# Hive_Max_Masse_neu4a.net
KiCad netlist of a schematic drawn in EAGLE
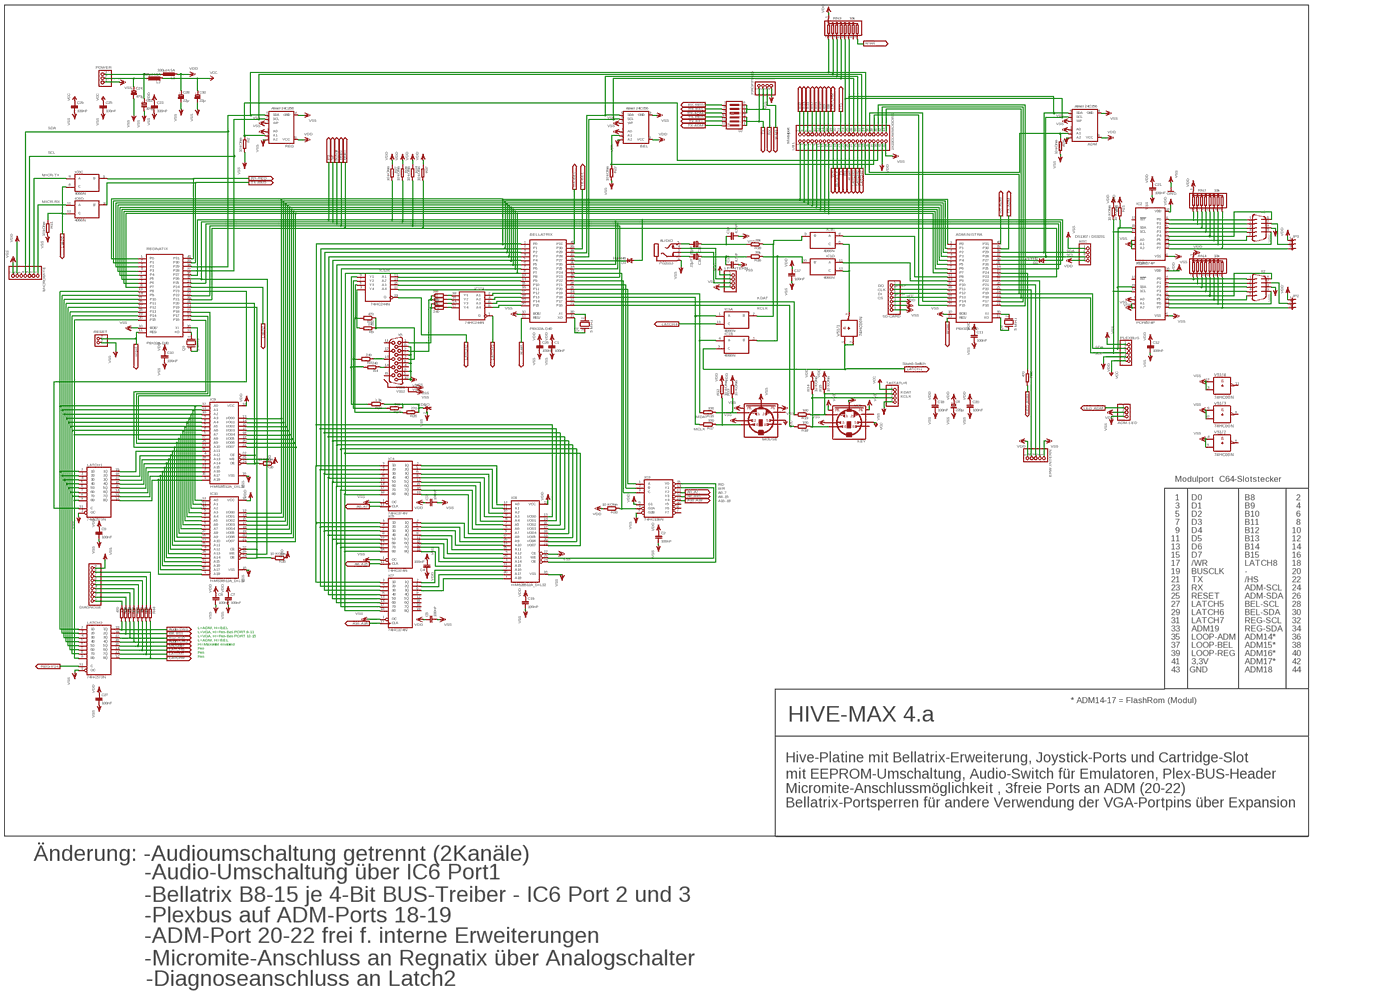
[diagram p0: schematic, sheet 1, overview]
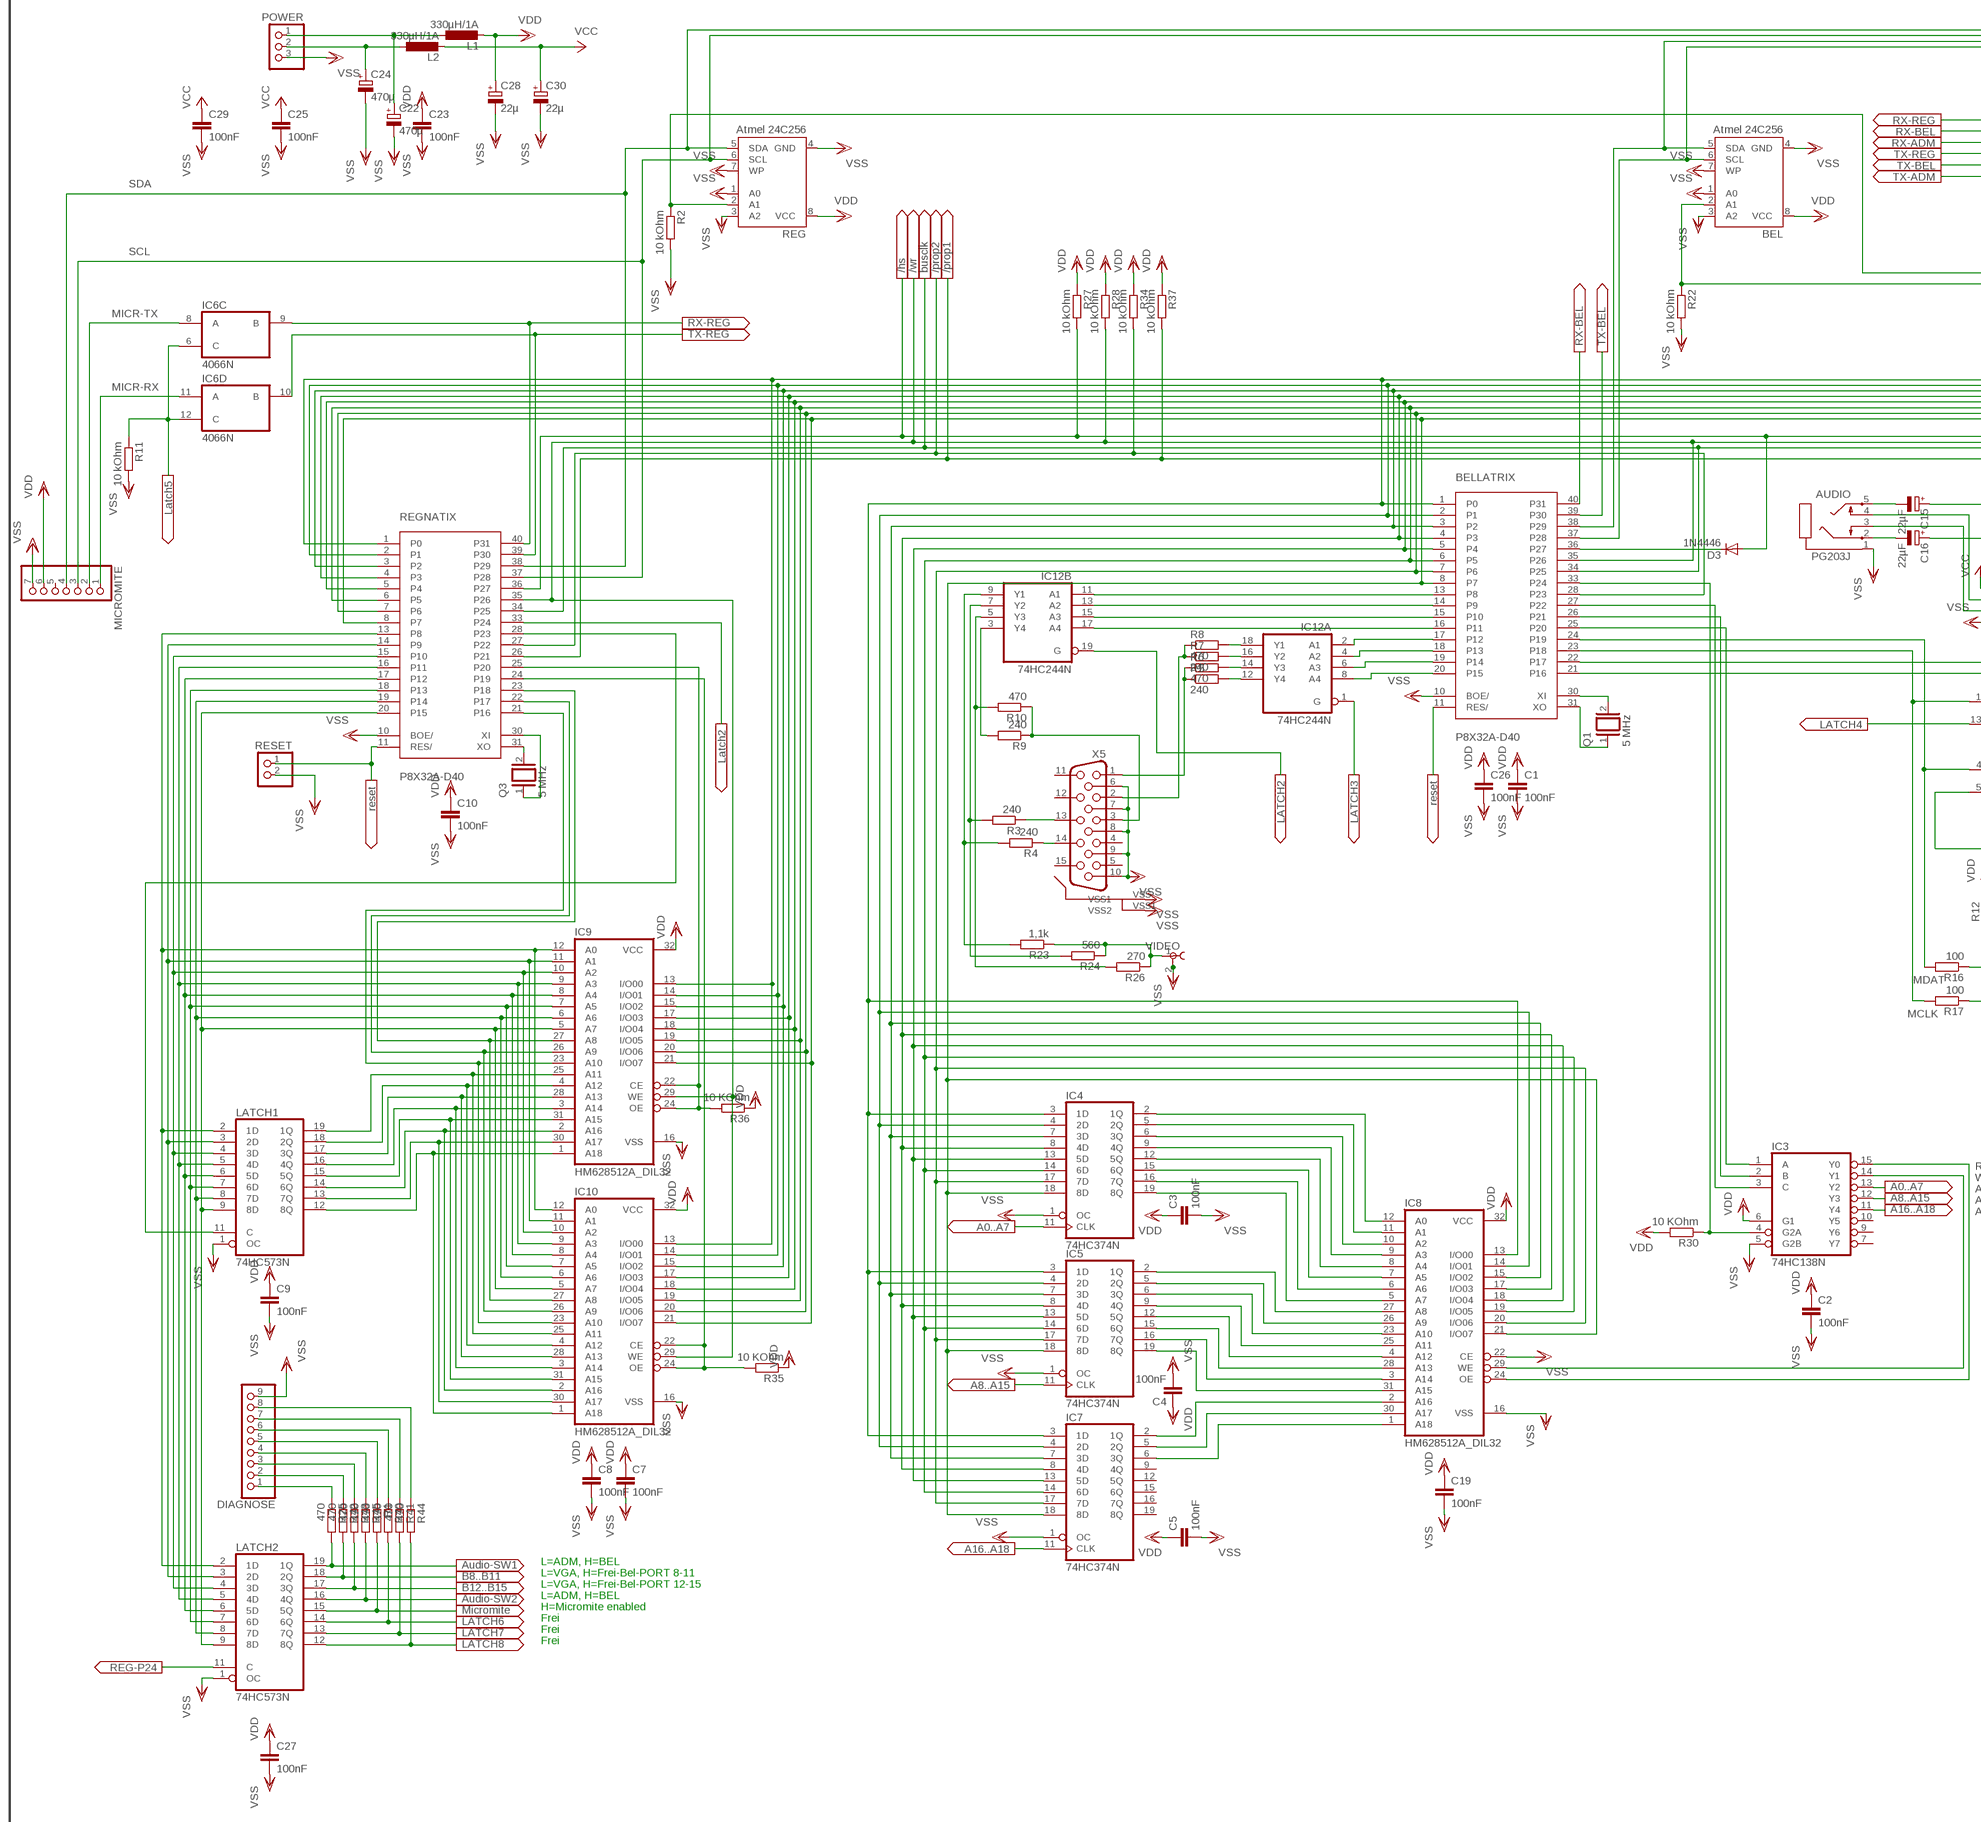
[diagram p1: schematic, sheet 1, part 1 of 4]
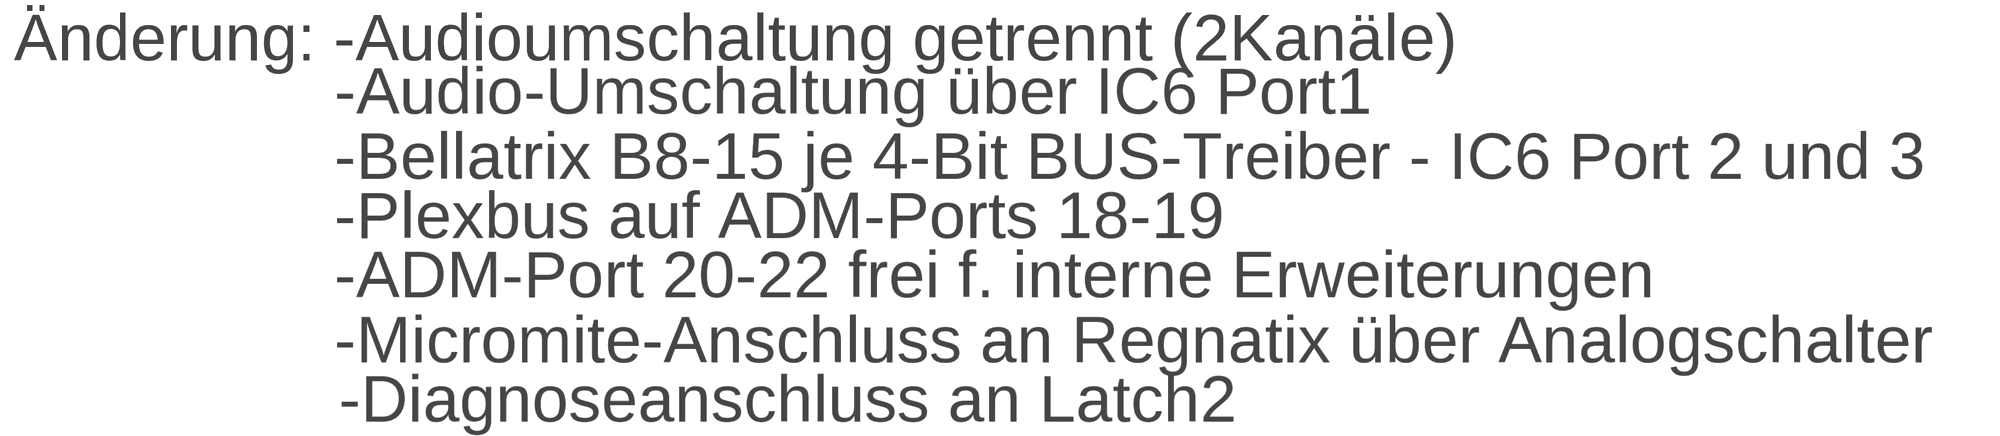
[diagram p2: schematic, sheet 1, part 2 of 4]
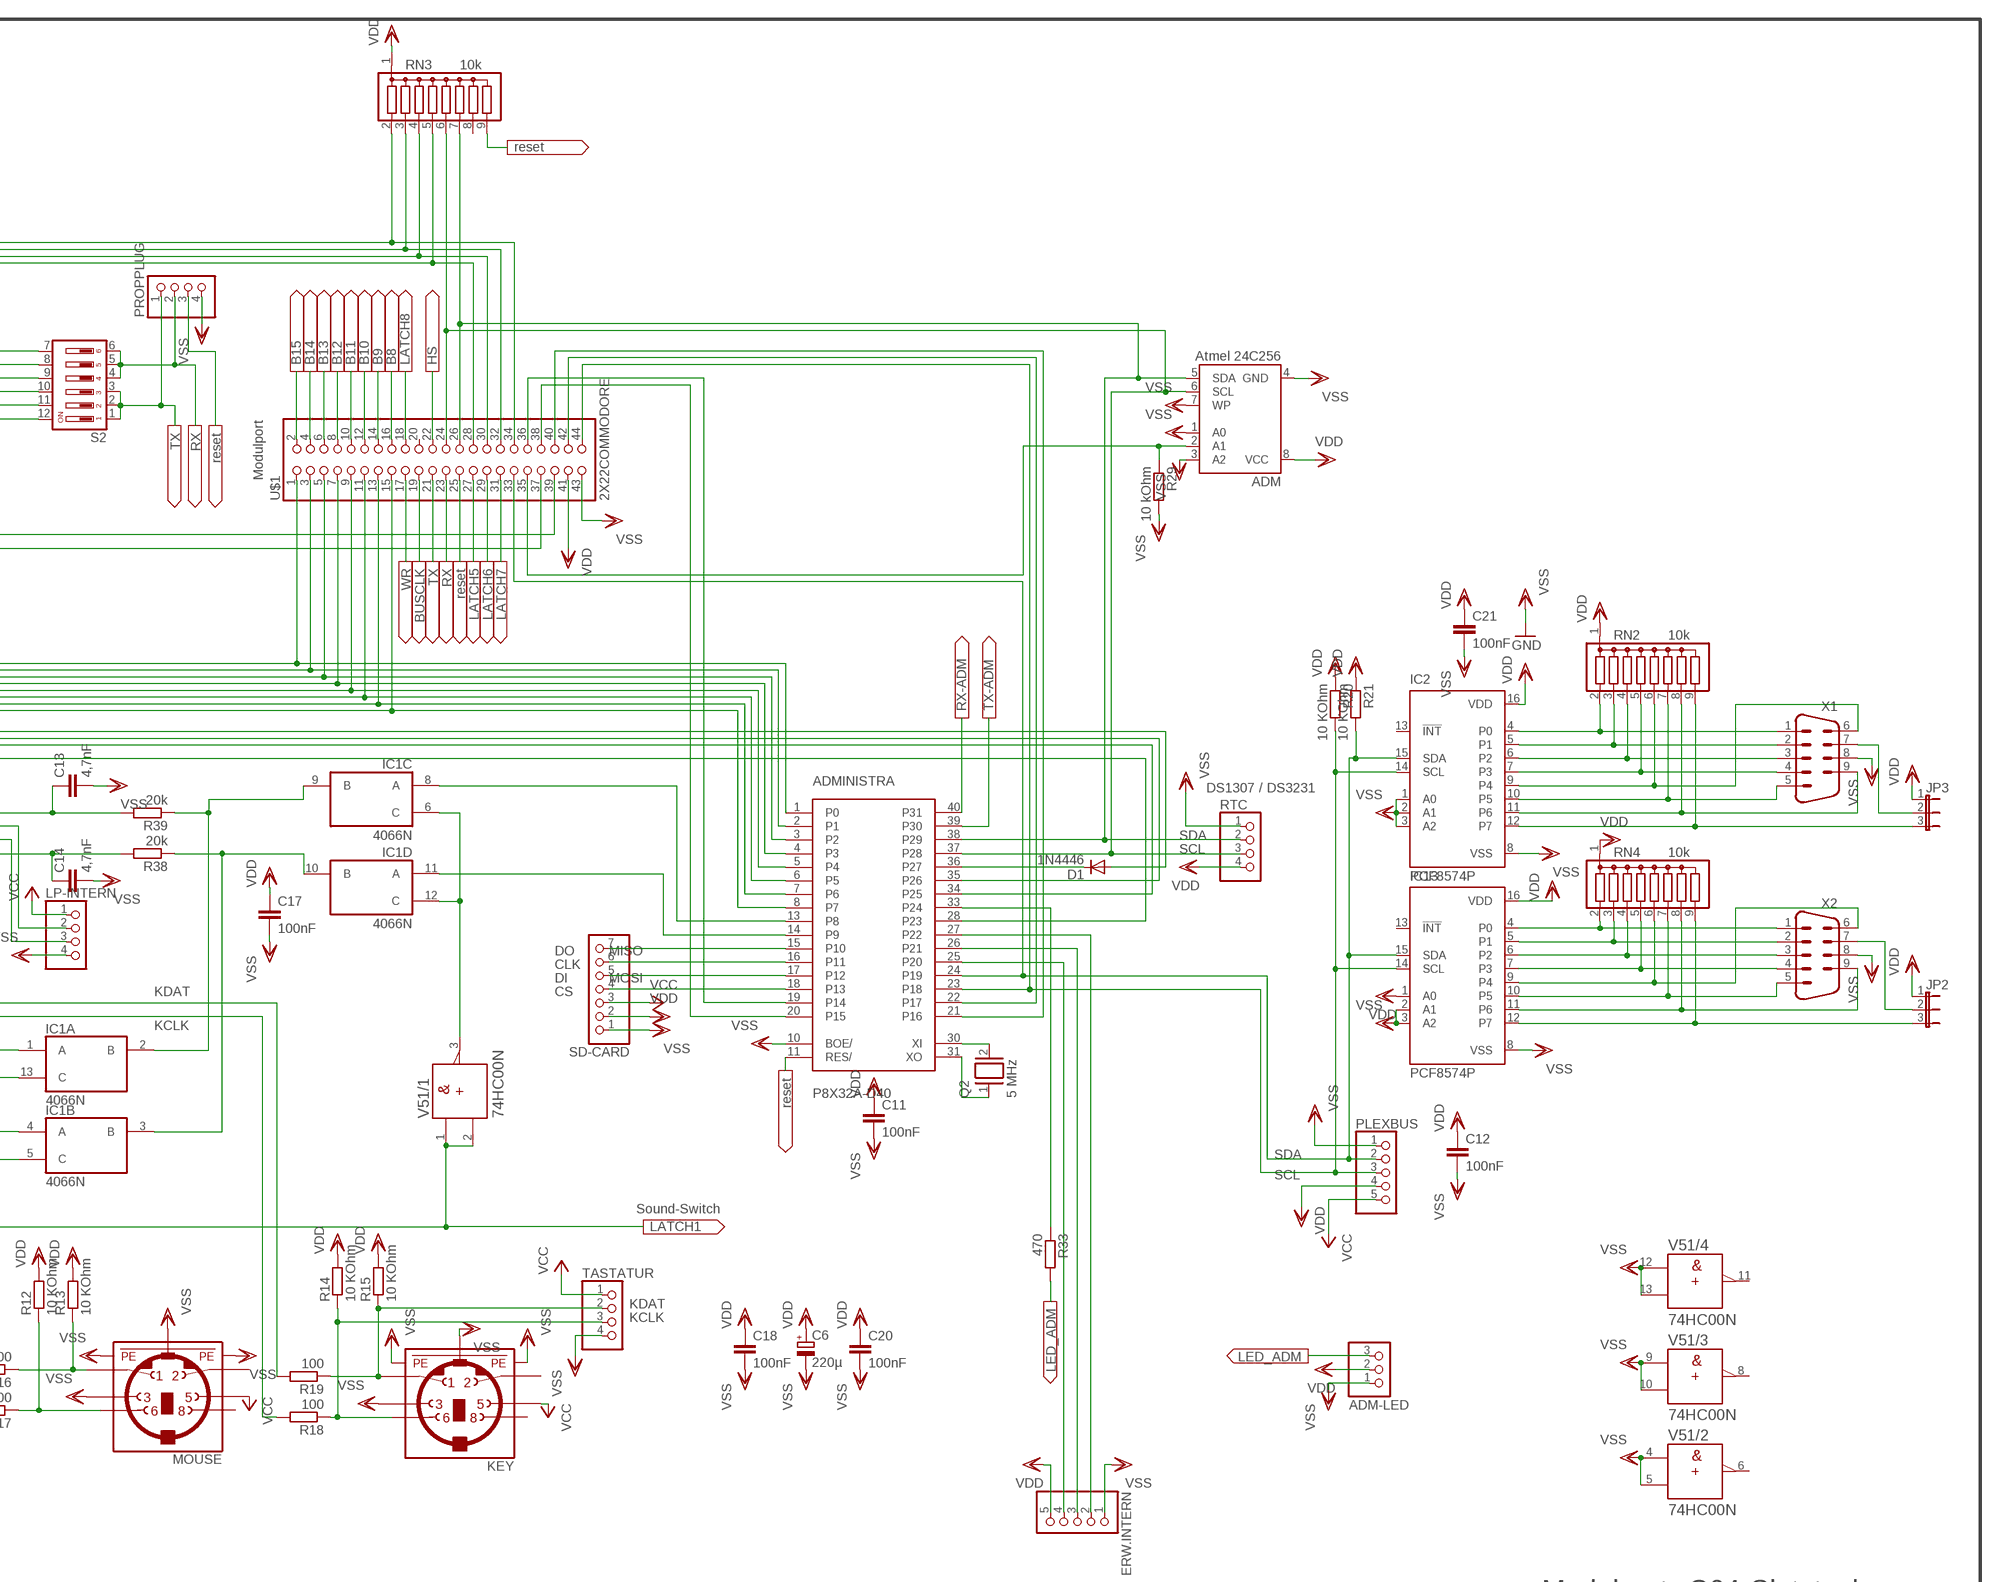
[diagram p3: schematic, sheet 1, part 3 of 4]
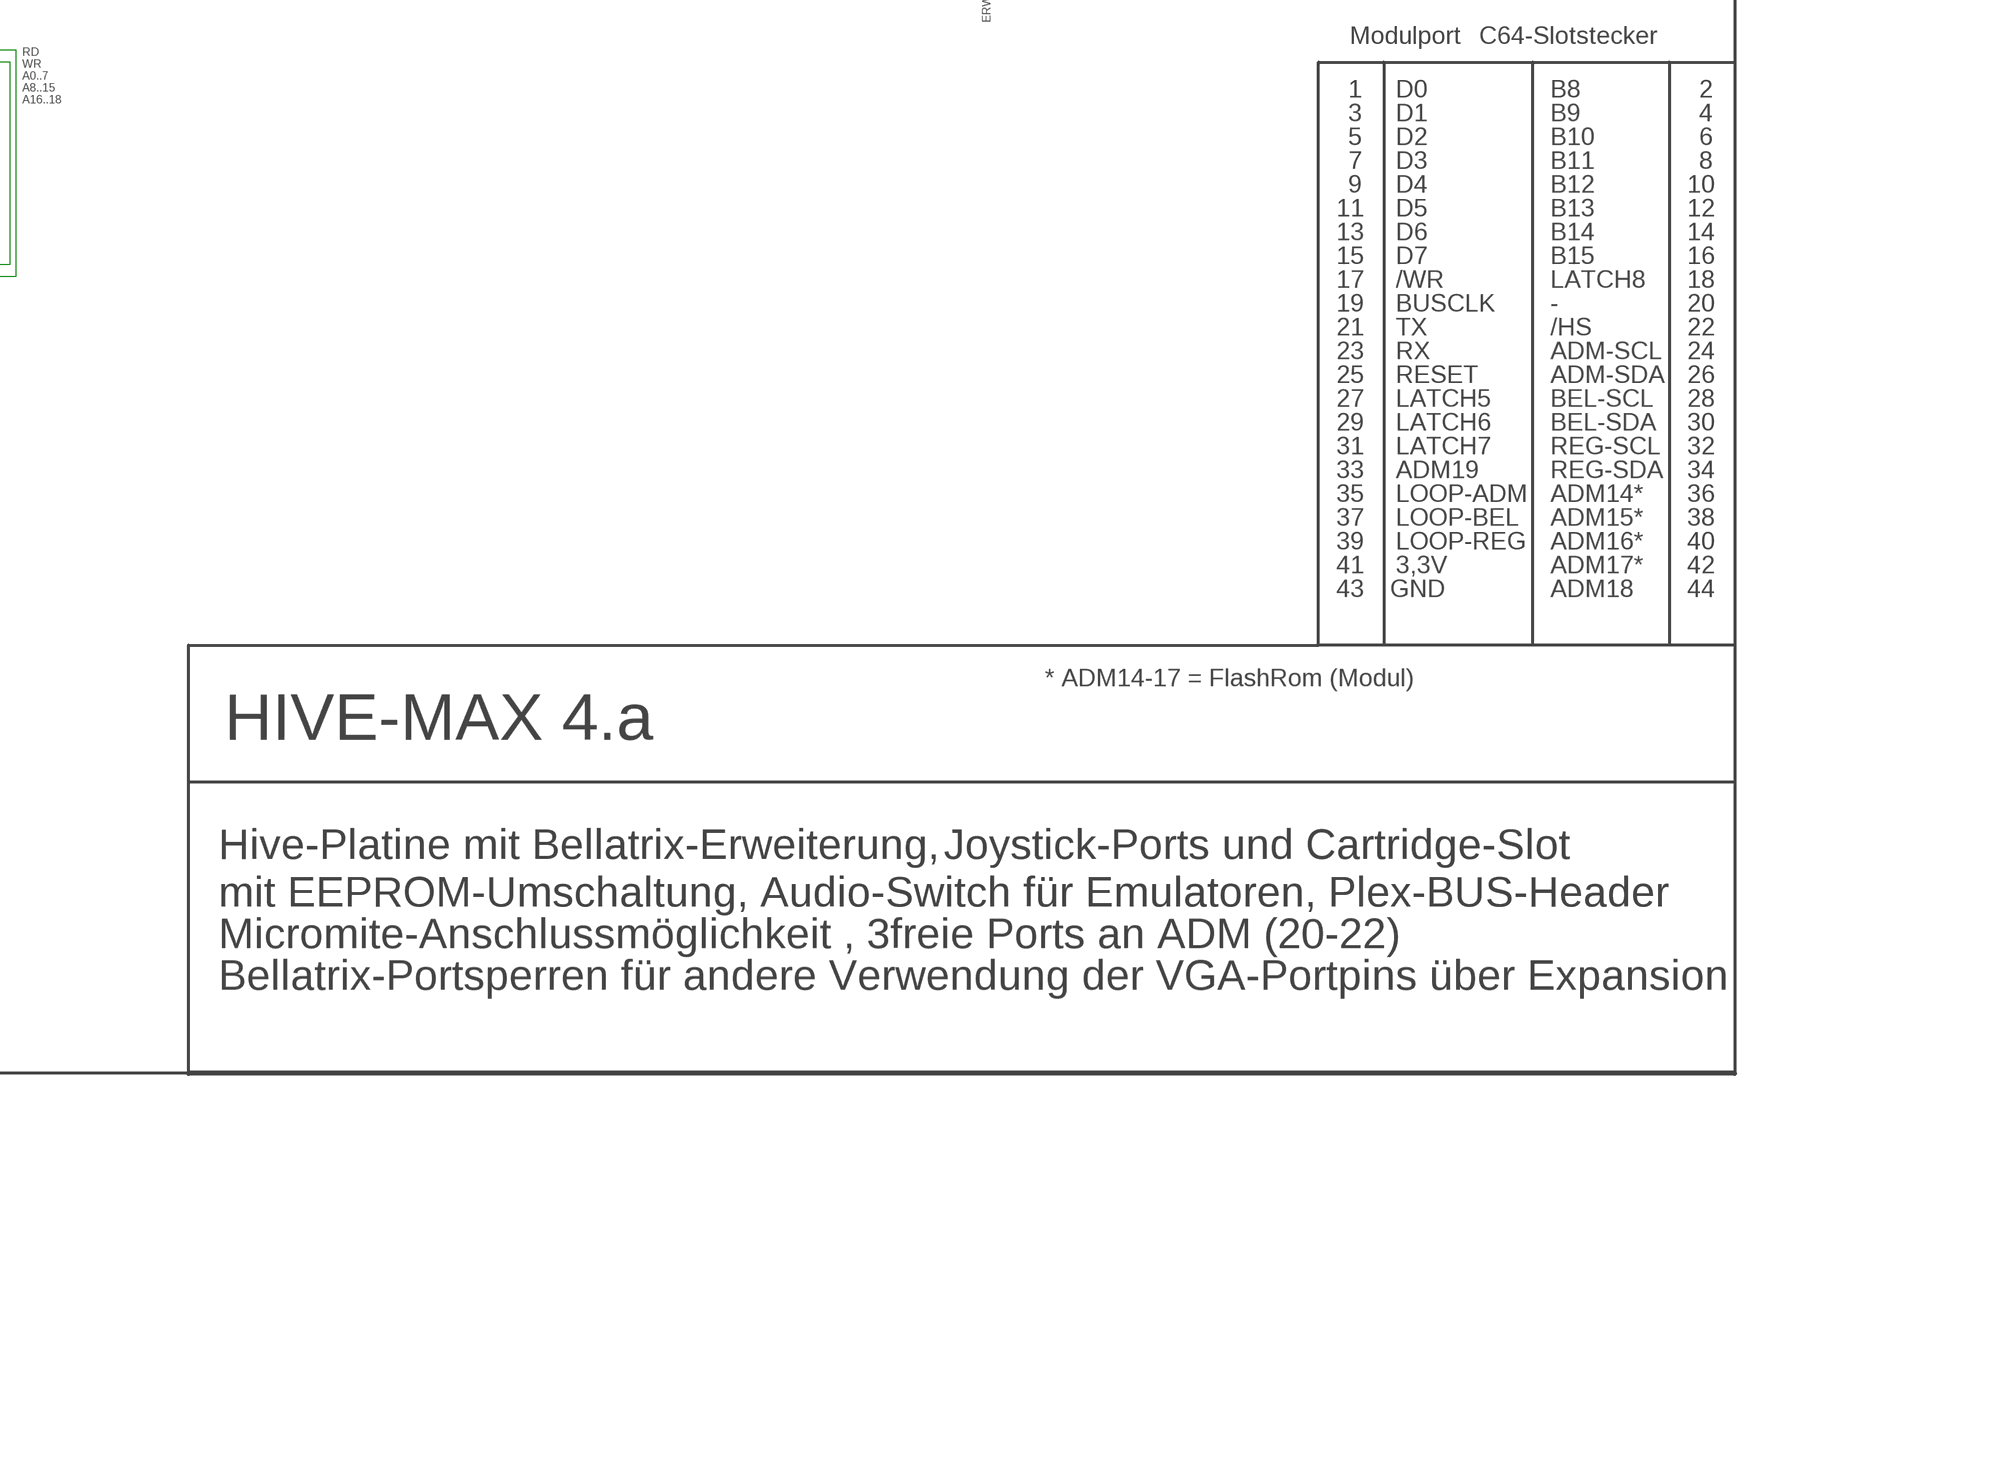
[diagram p4: schematic, sheet 1, part 4 of 4]

(export (version "E")
  (design (tool "Eeschema 10.0.6"))
  (components
    (comp (ref "ADM")
      (value "Atmel 24C256")
      (footprint "eagle-import:DIL08")
      (libsource (lib "eagle-import") (part "AT24CP"))
    )
    (comp (ref "ADM-LED")
      (value "PINHD-1X3")
      (footprint "eagle-import:1X03")
      (libsource (lib "eagle-import") (part "PINHD-1X3"))
    )
    (comp (ref "ADMINISTRA")
      (value "P8X32A-D40")
      (footprint "eagle-import:P8X32A-D40")
      (libsource (lib "eagle-import") (part "P8X32A-D40"))
    )
    (comp (ref "AUDIO")
      (value "PG203J")
      (footprint "eagle-import:PG203J")
      (libsource (lib "eagle-import") (part "PG203J"))
    )
    (comp (ref "BEL")
      (value "Atmel 24C256")
      (footprint "eagle-import:DIL08")
      (libsource (lib "eagle-import") (part "AT24CP"))
    )
    (comp (ref "BELLATRIX")
      (value "P8X32A-D40")
      (footprint "eagle-import:P8X32A-D40")
      (libsource (lib "eagle-import") (part "P8X32A-D40"))
    )
    (comp (ref "C1")
      (value "100nF")
      (footprint "eagle-import:C025-030X050")
      (libsource (lib "eagle-import") (part "C-EU025-030X050"))
    )
    (comp (ref "C2")
      (value "100nF")
      (footprint "eagle-import:C025-030X050")
      (libsource (lib "eagle-import") (part "C-EU025-030X050"))
    )
    (comp (ref "C3")
      (value "100nF")
      (footprint "eagle-import:C025-030X050")
      (libsource (lib "eagle-import") (part "C-EU025-030X050"))
    )
    (comp (ref "C4")
      (value "100nF")
      (footprint "eagle-import:C025-030X050")
      (libsource (lib "eagle-import") (part "C-EU025-030X050"))
    )
    (comp (ref "C5")
      (value "100nF")
      (footprint "eagle-import:C025-030X050")
      (libsource (lib "eagle-import") (part "C-EU025-030X050"))
    )
    (comp (ref "C6")
      (value "220µ")
      (footprint "eagle-import:E5-8,5")
      (libsource (lib "eagle-import") (part "CPOL-EUE5-8.5"))
    )
    (comp (ref "C7")
      (value "100nF")
      (footprint "eagle-import:C025-030X050")
      (libsource (lib "eagle-import") (part "C-EU025-030X050"))
    )
    (comp (ref "C8")
      (value "100nF")
      (footprint "eagle-import:C025-030X050")
      (libsource (lib "eagle-import") (part "C-EU025-030X050"))
    )
    (comp (ref "C9")
      (value "100nF")
      (footprint "eagle-import:C025-030X050")
      (libsource (lib "eagle-import") (part "C-EU025-030X050"))
    )
    (comp (ref "C10")
      (value "100nF")
      (footprint "eagle-import:C025-030X050")
      (libsource (lib "eagle-import") (part "C-EU025-030X050"))
    )
    (comp (ref "C11")
      (value "100nF")
      (footprint "eagle-import:C025-030X050")
      (libsource (lib "eagle-import") (part "C-EU025-030X050"))
    )
    (comp (ref "C12")
      (value "100nF")
      (footprint "eagle-import:C025-030X050")
      (libsource (lib "eagle-import") (part "C-EU025-030X050"))
    )
    (comp (ref "C13")
      (value "4,7nF")
      (footprint "eagle-import:C025-030X050")
      (libsource (lib "eagle-import") (part "C-EU025-030X050"))
    )
    (comp (ref "C14")
      (value "4,7nF")
      (footprint "eagle-import:C025-030X050")
      (libsource (lib "eagle-import") (part "C-EU025-030X050"))
    )
    (comp (ref "C15")
      (value "22µF")
      (footprint "eagle-import:E2-5")
      (libsource (lib "eagle-import") (part "CPOL-EUE2-5"))
    )
    (comp (ref "C16")
      (value "22µF")
      (footprint "eagle-import:E2-5")
      (libsource (lib "eagle-import") (part "CPOL-EUE2-5"))
    )
    (comp (ref "C17")
      (value "100nF")
      (footprint "eagle-import:C025-030X050")
      (libsource (lib "eagle-import") (part "C-EU025-030X050"))
    )
    (comp (ref "C18")
      (value "100nF")
      (footprint "eagle-import:C025-030X050")
      (libsource (lib "eagle-import") (part "C-EU025-030X050"))
    )
    (comp (ref "C19")
      (value "100nF")
      (footprint "eagle-import:C025-030X050")
      (libsource (lib "eagle-import") (part "C-EU025-030X050"))
    )
    (comp (ref "C20")
      (value "100nF")
      (footprint "eagle-import:C025-030X050")
      (libsource (lib "eagle-import") (part "C-EU025-030X050"))
    )
    (comp (ref "C21")
      (value "100nF")
      (footprint "eagle-import:C025-030X050")
      (libsource (lib "eagle-import") (part "C-EU025-030X050"))
    )
    (comp (ref "C22")
      (value "470µ")
      (footprint "eagle-import:E5-8,5")
      (libsource (lib "eagle-import") (part "CPOL-EUE5-8.5"))
    )
    (comp (ref "C23")
      (value "100nF")
      (footprint "eagle-import:C025-030X050")
      (libsource (lib "eagle-import") (part "C-EU025-030X050"))
    )
    (comp (ref "C24")
      (value "470µ")
      (footprint "eagle-import:E5-8,5")
      (libsource (lib "eagle-import") (part "CPOL-EUE5-8.5"))
    )
    (comp (ref "C25")
      (value "100nF")
      (footprint "eagle-import:C025-030X050")
      (libsource (lib "eagle-import") (part "C-EU025-030X050"))
    )
    (comp (ref "C26")
      (value "100nF")
      (footprint "eagle-import:C025-030X050")
      (libsource (lib "eagle-import") (part "C-EU025-030X050"))
    )
    (comp (ref "C27")
      (value "100nF")
      (footprint "eagle-import:C025-030X050")
      (libsource (lib "eagle-import") (part "C-EU025-030X050"))
    )
    (comp (ref "C28")
      (value "22µ")
      (footprint "eagle-import:E2-5")
      (libsource (lib "eagle-import") (part "CPOL-EUE2-5"))
    )
    (comp (ref "C29")
      (value "100nF")
      (footprint "eagle-import:C025-030X050")
      (libsource (lib "eagle-import") (part "C-EU025-030X050"))
    )
    (comp (ref "C30")
      (value "22µ")
      (footprint "eagle-import:E2-5")
      (libsource (lib "eagle-import") (part "CPOL-EUE2-5"))
    )
    (comp (ref "D1")
      (value "1N4446")
      (footprint "eagle-import:DO35-10")
      (libsource (lib "eagle-import") (part "1N4446"))
    )
    (comp (ref "D3")
      (value "1N4446")
      (footprint "eagle-import:DO35-10")
      (libsource (lib "eagle-import") (part "1N4446"))
    )
    (comp (ref "DIAGNOSE")
      (value "PINHD-1X9")
      (footprint "eagle-import:1X09")
      (libsource (lib "eagle-import") (part "PINHD-1X9"))
    )
    (comp (ref "ERW.INTERN")
      (value "PINHD-1X5")
      (footprint "eagle-import:1X05")
      (libsource (lib "eagle-import") (part "PINHD-1X5"))
    )
    (comp (ref "IC1")
      (value "4066N")
      (footprint "eagle-import:DIL14")
      (libsource (lib "eagle-import") (part "4066N"))
    )
    (comp (ref "IC2")
      (value "PCF8574P")
      (footprint "eagle-import:DIL16")
      (fields (field (name "MPN") "PCF8574PN"))
      (libsource (lib "eagle-import") (part "PCF8574P"))
    )
    (comp (ref "IC3")
      (value "74HC138N")
      (footprint "eagle-import:DIL16")
      (libsource (lib "eagle-import") (part "74138NHC"))
    )
    (comp (ref "IC4")
      (value "74HC374N")
      (footprint "eagle-import:DIL20")
      (libsource (lib "eagle-import") (part "74374NHC"))
    )
    (comp (ref "IC5")
      (value "74HC374N")
      (footprint "eagle-import:DIL20")
      (libsource (lib "eagle-import") (part "74374NHC"))
    )
    (comp (ref "IC6")
      (value "4066N")
      (footprint "eagle-import:DIL14")
      (libsource (lib "eagle-import") (part "4066N"))
    )
    (comp (ref "IC7")
      (value "74HC374N")
      (footprint "eagle-import:DIL20")
      (libsource (lib "eagle-import") (part "74374NHC"))
    )
    (comp (ref "IC8")
      (value "HM628512A_DIL32")
      (footprint "eagle-import:DIL32")
      (libsource (lib "eagle-import") (part "HM628512A_DIL32"))
    )
    (comp (ref "IC9")
      (value "HM628512A_DIL32")
      (footprint "eagle-import:DIL32")
      (libsource (lib "eagle-import") (part "HM628512A_DIL32"))
    )
    (comp (ref "IC10")
      (value "HM628512A_DIL32")
      (footprint "eagle-import:DIL32")
      (libsource (lib "eagle-import") (part "HM628512A_DIL32"))
    )
    (comp (ref "IC12")
      (value "74HC244N")
      (footprint "eagle-import:DIL20")
      (libsource (lib "eagle-import") (part "74244NHC"))
    )
    (comp (ref "IC13")
      (value "PCF8574P")
      (footprint "eagle-import:DIL16")
      (fields (field (name "MPN") "PCF8574PN"))
      (libsource (lib "eagle-import") (part "PCF8574P"))
    )
    (comp (ref "JP2")
      (value "JP2E")
      (footprint "eagle-import:JP2")
      (libsource (lib "eagle-import") (part "JP2E"))
    )
    (comp (ref "JP3")
      (value "JP2E")
      (footprint "eagle-import:JP2")
      (libsource (lib "eagle-import") (part "JP2E"))
    )
    (comp (ref "KEY")
      (value "MINI_DIN_6")
      (footprint "eagle-import:M_DIN6")
      (libsource (lib "eagle-import") (part "MINI_DIN_6"))
    )
    (comp (ref "L1")
      (value "330µH/1A")
      (footprint "eagle-import:6000-XXXX-RC")
      (libsource (lib "eagle-import") (part "L-EU6000-XXX-RC"))
    )
    (comp (ref "L2")
      (value "330µH/1A")
      (footprint "eagle-import:6000-XXXX-RC")
      (libsource (lib "eagle-import") (part "L-EU6000-XXX-RC"))
    )
    (comp (ref "LATCH1")
      (value "74HC573N")
      (footprint "eagle-import:DIL20")
      (libsource (lib "eagle-import") (part "74573NHC"))
    )
    (comp (ref "LATCH2")
      (value "74HC573N")
      (footprint "eagle-import:DIL20")
      (libsource (lib "eagle-import") (part "74573NHC"))
    )
    (comp (ref "LP-INTERN")
      (value "PINHD-1X4")
      (footprint "eagle-import:1X04")
      (libsource (lib "eagle-import") (part "PINHD-1X4"))
    )
    (comp (ref "MICROMITE")
      (value "PINHD-1X7")
      (footprint "eagle-import:1X07")
      (libsource (lib "eagle-import") (part "PINHD-1X7"))
    )
    (comp (ref "MOUSE")
      (value "MINI_DIN_6")
      (footprint "eagle-import:M_DIN6")
      (libsource (lib "eagle-import") (part "MINI_DIN_6"))
    )
    (comp (ref "PLEXBUS")
      (value "PINHD-1X5")
      (footprint "eagle-import:1X05")
      (libsource (lib "eagle-import") (part "PINHD-1X5"))
    )
    (comp (ref "POWER")
      (value "PINHD-1X3")
      (footprint "eagle-import:1X03")
      (libsource (lib "eagle-import") (part "PINHD-1X3"))
    )
    (comp (ref "PROPPLUG")
      (value "PINHD-1X4/90")
      (footprint "eagle-import:1X04_90")
      (libsource (lib "eagle-import") (part "PINHD-1X4/90"))
    )
    (comp (ref "Q1")
      (value "5 MHz")
      (footprint "eagle-import:QS")
      (libsource (lib "eagle-import") (part "XTAL/S"))
    )
    (comp (ref "Q2")
      (value "5 MHz")
      (footprint "eagle-import:QS")
      (libsource (lib "eagle-import") (part "XTAL/S"))
    )
    (comp (ref "Q3")
      (value "5 MHz")
      (footprint "eagle-import:QS")
      (libsource (lib "eagle-import") (part "XTAL/S"))
    )
    (comp (ref "R1")
      (value "470")
      (footprint "eagle-import:0204V")
      (libsource (lib "eagle-import") (part "R-EU_0204/2V"))
    )
    (comp (ref "R2")
      (value "10 kOhm")
      (footprint "eagle-import:0204V")
      (libsource (lib "eagle-import") (part "R-EU_0204/2V"))
    )
    (comp (ref "R3")
      (value "240")
      (footprint "eagle-import:0204V")
      (libsource (lib "eagle-import") (part "R-EU_0204/2V"))
    )
    (comp (ref "R4")
      (value "240")
      (footprint "eagle-import:0204V")
      (libsource (lib "eagle-import") (part "R-EU_0204/2V"))
    )
    (comp (ref "R5")
      (value "240")
      (footprint "eagle-import:0204V")
      (libsource (lib "eagle-import") (part "R-EU_0204/2V"))
    )
    (comp (ref "R6")
      (value "470")
      (footprint "eagle-import:0204V")
      (libsource (lib "eagle-import") (part "R-EU_0204/2V"))
    )
    (comp (ref "R7")
      (value "240")
      (footprint "eagle-import:0204V")
      (libsource (lib "eagle-import") (part "R-EU_0204/2V"))
    )
    (comp (ref "R8")
      (value "470")
      (footprint "eagle-import:0204V")
      (libsource (lib "eagle-import") (part "R-EU_0204/2V"))
    )
    (comp (ref "R9")
      (value "240")
      (footprint "eagle-import:0204V")
      (libsource (lib "eagle-import") (part "R-EU_0204/2V"))
    )
    (comp (ref "R10")
      (value "470")
      (footprint "eagle-import:0204V")
      (libsource (lib "eagle-import") (part "R-EU_0204/2V"))
    )
    (comp (ref "R11")
      (value "10 kOhm")
      (footprint "eagle-import:0204V")
      (libsource (lib "eagle-import") (part "R-EU_0204/2V"))
    )
    (comp (ref "R12")
      (value "10 KOhm")
      (footprint "eagle-import:0204V")
      (libsource (lib "eagle-import") (part "R-EU_0204/2V"))
    )
    (comp (ref "R13")
      (value "10 KOhm")
      (footprint "eagle-import:0204V")
      (libsource (lib "eagle-import") (part "R-EU_0204/2V"))
    )
    (comp (ref "R14")
      (value "10 KOhm")
      (footprint "eagle-import:0204V")
      (libsource (lib "eagle-import") (part "R-EU_0204/2V"))
    )
    (comp (ref "R15")
      (value "10 KOhm")
      (footprint "eagle-import:0204V")
      (libsource (lib "eagle-import") (part "R-EU_0204/2V"))
    )
    (comp (ref "R16")
      (value "100")
      (footprint "eagle-import:0204V")
      (libsource (lib "eagle-import") (part "R-EU_0204/2V"))
    )
    (comp (ref "R17")
      (value "100")
      (footprint "eagle-import:0204V")
      (libsource (lib "eagle-import") (part "R-EU_0204/2V"))
    )
    (comp (ref "R18")
      (value "100")
      (footprint "eagle-import:0204V")
      (libsource (lib "eagle-import") (part "R-EU_0204/2V"))
    )
    (comp (ref "R19")
      (value "100")
      (footprint "eagle-import:0204V")
      (libsource (lib "eagle-import") (part "R-EU_0204/2V"))
    )
    (comp (ref "R20")
      (value "10 KOhm")
      (footprint "eagle-import:0204V")
      (libsource (lib "eagle-import") (part "R-EU_0204/2V"))
    )
    (comp (ref "R21")
      (value "10 KOhm")
      (footprint "eagle-import:0204V")
      (libsource (lib "eagle-import") (part "R-EU_0204/2V"))
    )
    (comp (ref "R22")
      (value "10 kOhm")
      (footprint "eagle-import:0204V")
      (libsource (lib "eagle-import") (part "R-EU_0204/2V"))
    )
    (comp (ref "R23")
      (value "1,1k")
      (footprint "eagle-import:0204V")
      (libsource (lib "eagle-import") (part "R-EU_0204/2V"))
    )
    (comp (ref "R24")
      (value "560")
      (footprint "eagle-import:0204V")
      (libsource (lib "eagle-import") (part "R-EU_0204/2V"))
    )
    (comp (ref "R25")
      (value "470")
      (footprint "eagle-import:0204V")
      (libsource (lib "eagle-import") (part "R-EU_0204/2V"))
    )
    (comp (ref "R26")
      (value "270")
      (footprint "eagle-import:0204V")
      (libsource (lib "eagle-import") (part "R-EU_0204/2V"))
    )
    (comp (ref "R27")
      (value "10 kOhm")
      (footprint "eagle-import:0204V")
      (libsource (lib "eagle-import") (part "R-EU_0204/2V"))
    )
    (comp (ref "R28")
      (value "10 kOhm")
      (footprint "eagle-import:0204V")
      (libsource (lib "eagle-import") (part "R-EU_0204/2V"))
    )
    (comp (ref "R29")
      (value "10 kOhm")
      (footprint "eagle-import:0204V")
      (libsource (lib "eagle-import") (part "R-EU_0204/2V"))
    )
    (comp (ref "R30")
      (value "10 KOhm")
      (footprint "eagle-import:0204V")
      (libsource (lib "eagle-import") (part "R-EU_0204/2V"))
    )
    (comp (ref "R33")
      (value "470")
      (footprint "eagle-import:0204V")
      (libsource (lib "eagle-import") (part "R-EU_0204/2V"))
    )
    (comp (ref "R34")
      (value "10 kOhm")
      (footprint "eagle-import:0204V")
      (libsource (lib "eagle-import") (part "R-EU_0204/2V"))
    )
    (comp (ref "R35")
      (value "10 KOhm")
      (footprint "eagle-import:0204V")
      (libsource (lib "eagle-import") (part "R-EU_0204/2V"))
    )
    (comp (ref "R36")
      (value "10 KOhm")
      (footprint "eagle-import:0204V")
      (libsource (lib "eagle-import") (part "R-EU_0204/2V"))
    )
    (comp (ref "R37")
      (value "10 kOhm")
      (footprint "eagle-import:0204V")
      (libsource (lib "eagle-import") (part "R-EU_0204/2V"))
    )
    (comp (ref "R38")
      (value "20k")
      (footprint "eagle-import:0204V")
      (libsource (lib "eagle-import") (part "R-EU_0204/2V"))
    )
    (comp (ref "R39")
      (value "20k")
      (footprint "eagle-import:0204V")
      (libsource (lib "eagle-import") (part "R-EU_0204/2V"))
    )
    (comp (ref "R40")
      (value "470")
      (footprint "eagle-import:0204V")
      (libsource (lib "eagle-import") (part "R-EU_0204/2V"))
    )
    (comp (ref "R41")
      (value "470")
      (footprint "eagle-import:0204V")
      (libsource (lib "eagle-import") (part "R-EU_0204/2V"))
    )
    (comp (ref "R42")
      (value "470")
      (footprint "eagle-import:0204V")
      (libsource (lib "eagle-import") (part "R-EU_0204/2V"))
    )
    (comp (ref "R43")
      (value "470")
      (footprint "eagle-import:0204V")
      (libsource (lib "eagle-import") (part "R-EU_0204/2V"))
    )
    (comp (ref "R44")
      (value "470")
      (footprint "eagle-import:0204V")
      (libsource (lib "eagle-import") (part "R-EU_0204/2V"))
    )
    (comp (ref "R45")
      (value "470")
      (footprint "eagle-import:0204V")
      (libsource (lib "eagle-import") (part "R-EU_0204/2V"))
    )
    (comp (ref "REG")
      (value "Atmel 24C256")
      (footprint "eagle-import:DIL08")
      (libsource (lib "eagle-import") (part "AT24CP"))
    )
    (comp (ref "REGNATIX")
      (value "P8X32A-D40")
      (footprint "eagle-import:P8X32A-D40")
      (libsource (lib "eagle-import") (part "P8X32A-D40"))
    )
    (comp (ref "RESET")
      (value "PINHD-1X2")
      (footprint "eagle-import:1X02")
      (libsource (lib "eagle-import") (part "PINHD-1X2"))
    )
    (comp (ref "RN2")
      (value "10k")
      (footprint "eagle-import:SIL9")
      (libsource (lib "eagle-import") (part "G08R"))
    )
    (comp (ref "RN3")
      (value "10k")
      (footprint "eagle-import:SIL9")
      (libsource (lib "eagle-import") (part "G08R"))
    )
    (comp (ref "RN4")
      (value "10k")
      (footprint "eagle-import:SIL9")
      (libsource (lib "eagle-import") (part "G08R"))
    )
    (comp (ref "RTC")
      (value "PINHD-1X4")
      (footprint "eagle-import:1X04")
      (libsource (lib "eagle-import") (part "PINHD-1X4"))
    )
    (comp (ref "S2")
      (value "DA06")
      (footprint "eagle-import:DA-06")
      (fields (field (name "MPN") "MCDA06"))
      (libsource (lib "eagle-import") (part "DA06"))
    )
    (comp (ref "SD-CARD")
      (value "PINHD-1X7")
      (footprint "eagle-import:1X07")
      (libsource (lib "eagle-import") (part "PINHD-1X7"))
    )
    (comp (ref "TASTATUR")
      (value "PINHD-1X4")
      (footprint "eagle-import:1X04")
      (libsource (lib "eagle-import") (part "PINHD-1X4"))
    )
    (comp (ref "U$1")
      (value "2X22COMMODORE")
      (footprint "eagle-import:2X22-COMMODORE")
      (libsource (lib "eagle-import") (part "2X22COMMODORE"))
    )
    (comp (ref "V51")
      (value "74HC00N")
      (footprint "eagle-import:DIL14")
      (libsource (lib "eagle-import") (part "7400NHC"))
    )
    (comp (ref "VIDEO")
      (value "CINCHFEM")
      (footprint "eagle-import:TOBU3")
      (libsource (lib "eagle-import") (part "CINCHFEM"))
    )
    (comp (ref "X1")
      (value "M09HP")
      (footprint "eagle-import:M09HP")
      (libsource (lib "eagle-import") (part "M09HP"))
    )
    (comp (ref "X2")
      (value "M09HP")
      (footprint "eagle-import:M09HP")
      (libsource (lib "eagle-import") (part "M09HP"))
    )
    (comp (ref "X5")
      (value "HF15H")
      (footprint "eagle-import:HDF15H")
      (libsource (lib "eagle-import") (part "HF15H"))
    )
  )
  (nets
    (net (code "1") (name "/A0..A7") (class "Default")
      (node (ref "IC3") (pin "13") (pinfunction "Y2_13") (pintype "output"))
      (node (ref "IC4") (pin "11") (pinfunction "CLK_11") (pintype "input"))
    )
    (net (code "2") (name "/A8..A15") (class "Default")
      (node (ref "IC3") (pin "12") (pinfunction "Y3_12") (pintype "output"))
      (node (ref "IC5") (pin "11") (pinfunction "CLK_11") (pintype "input"))
    )
    (net (code "3") (name "/A16..A18") (class "Default")
      (node (ref "IC3") (pin "11") (pinfunction "Y4_11") (pintype "output"))
      (node (ref "IC7") (pin "11") (pinfunction "CLK_11") (pintype "input"))
    )
    (net (code "4") (name "/B8") (class "Default")
      (node (ref "BELLATRIX") (pin "13") (pinfunction "P8_13") (pintype "bidirectional"))
      (node (ref "IC12") (pin "11") (pinfunction "A1_11") (pintype "input"))
      (node (ref "U$1") (pin "16") (pinfunction "16_16") (pintype "passive"))
    )
    (net (code "5") (name "/B9") (class "Default")
      (node (ref "BELLATRIX") (pin "14") (pinfunction "P9_14") (pintype "bidirectional"))
      (node (ref "IC12") (pin "13") (pinfunction "A2_13") (pintype "input"))
      (node (ref "U$1") (pin "14") (pinfunction "14_14") (pintype "passive"))
    )
    (net (code "6") (name "/B10") (class "Default")
      (node (ref "BELLATRIX") (pin "15") (pinfunction "P10_15") (pintype "bidirectional"))
      (node (ref "IC12") (pin "15") (pinfunction "A3_15") (pintype "input"))
      (node (ref "U$1") (pin "12") (pinfunction "12_12") (pintype "passive"))
    )
    (net (code "7") (name "/B11") (class "Default")
      (node (ref "BELLATRIX") (pin "16") (pinfunction "P11_16") (pintype "bidirectional"))
      (node (ref "IC12") (pin "17") (pinfunction "A4_17") (pintype "input"))
      (node (ref "U$1") (pin "10") (pinfunction "10_10") (pintype "passive"))
    )
    (net (code "8") (name "/B12") (class "Default")
      (node (ref "BELLATRIX") (pin "17") (pinfunction "P12_17") (pintype "bidirectional"))
      (node (ref "IC12") (pin "2") (pinfunction "A1_2") (pintype "input"))
      (node (ref "U$1") (pin "8") (pinfunction "8_8") (pintype "passive"))
    )
    (net (code "9") (name "/B13") (class "Default")
      (node (ref "BELLATRIX") (pin "18") (pinfunction "P13_18") (pintype "bidirectional"))
      (node (ref "IC12") (pin "4") (pinfunction "A2_4") (pintype "input"))
      (node (ref "U$1") (pin "6") (pinfunction "6_6") (pintype "passive"))
    )
    (net (code "10") (name "/B14") (class "Default")
      (node (ref "BELLATRIX") (pin "19") (pinfunction "P14_19") (pintype "bidirectional"))
      (node (ref "IC12") (pin "6") (pinfunction "A3_6") (pintype "input"))
      (node (ref "U$1") (pin "4") (pinfunction "4_4") (pintype "passive"))
    )
    (net (code "11") (name "/B15") (class "Default")
      (node (ref "BELLATRIX") (pin "20") (pinfunction "P15_20") (pintype "bidirectional"))
      (node (ref "IC12") (pin "8") (pinfunction "A4_8") (pintype "input"))
      (node (ref "U$1") (pin "2") (pinfunction "2_2") (pintype "passive"))
    )
    (net (code "12") (name "/BUSCLK") (class "Default")
      (node (ref "ADMINISTRA") (pin "34") (pinfunction "P25_34") (pintype "bidirectional"))
      (node (ref "BELLATRIX") (pin "34") (pinfunction "P25_34") (pintype "bidirectional"))
      (node (ref "REGNATIX") (pin "34") (pinfunction "P25_34") (pintype "bidirectional"))
      (node (ref "U$1") (pin "19") (pinfunction "19_19") (pintype "passive"))
    )
    (net (code "13") (name "/GLOB_RESET") (class "Default")
      (node (ref "ADMINISTRA") (pin "11") (pinfunction "RES/_11") (pintype "bidirectional"))
      (node (ref "BELLATRIX") (pin "11") (pinfunction "RES/_11") (pintype "bidirectional"))
      (node (ref "PROPPLUG") (pin "3") (pinfunction "3_3") (pintype "passive"))
      (node (ref "REGNATIX") (pin "11") (pinfunction "RES/_11") (pintype "bidirectional"))
      (node (ref "RESET") (pin "1") (pinfunction "1_1") (pintype "passive"))
      (node (ref "RN3") (pin "9") (pinfunction "9_9") (pintype "passive"))
      (node (ref "U$1") (pin "25") (pinfunction "25_25") (pintype "passive"))
    )
    (net (code "14") (name "/LATCH1") (class "Default")
      (node (ref "IC1") (pin "5") (pinfunction "C_5") (pintype "input"))
      (node (ref "LATCH2") (pin "19") (pinfunction "1Q_19") (pintype "tri_state"))
      (node (ref "R25") (pin "2") (pinfunction "2_2") (pintype "passive"))
      (node (ref "V51") (pin "1") (pinfunction "A_1") (pintype "input"))
      (node (ref "V51") (pin "2") (pinfunction "B_2") (pintype "input"))
    )
    (net (code "15") (name "/LATCH2") (class "Default")
      (node (ref "IC12") (pin "19") (pinfunction "G_19") (pintype "input"))
      (node (ref "LATCH2") (pin "18") (pinfunction "2Q_18") (pintype "tri_state"))
      (node (ref "R42") (pin "2") (pinfunction "2_2") (pintype "passive"))
    )
    (net (code "16") (name "/LATCH3") (class "Default")
      (node (ref "IC12") (pin "1") (pinfunction "G_1") (pintype "input"))
      (node (ref "LATCH2") (pin "17") (pinfunction "3Q_17") (pintype "tri_state"))
      (node (ref "R43") (pin "2") (pinfunction "2_2") (pintype "passive"))
    )
    (net (code "17") (name "/LATCH4") (class "Default")
      (node (ref "IC1") (pin "13") (pinfunction "C_13") (pintype "input"))
      (node (ref "LATCH2") (pin "16") (pinfunction "4Q_16") (pintype "tri_state"))
      (node (ref "R45") (pin "2") (pinfunction "2_2") (pintype "passive"))
    )
    (net (code "18") (name "/LATCH5") (class "Default")
      (node (ref "IC6") (pin "12") (pinfunction "C_12") (pintype "input"))
      (node (ref "IC6") (pin "6") (pinfunction "C_6") (pintype "input"))
      (node (ref "LATCH2") (pin "15") (pinfunction "5Q_15") (pintype "tri_state"))
      (node (ref "R1") (pin "2") (pinfunction "2_2") (pintype "passive"))
      (node (ref "R11") (pin "1") (pinfunction "1_1") (pintype "passive"))
      (node (ref "U$1") (pin "27") (pinfunction "27_27") (pintype "passive"))
    )
    (net (code "19") (name "/LATCH6") (class "Default")
      (node (ref "LATCH2") (pin "14") (pinfunction "6Q_14") (pintype "tri_state"))
      (node (ref "R40") (pin "2") (pinfunction "2_2") (pintype "passive"))
      (node (ref "U$1") (pin "29") (pinfunction "29_29") (pintype "passive"))
    )
    (net (code "20") (name "/LATCH7") (class "Default")
      (node (ref "LATCH2") (pin "13") (pinfunction "7Q_13") (pintype "tri_state"))
      (node (ref "R41") (pin "2") (pinfunction "2_2") (pintype "passive"))
      (node (ref "U$1") (pin "31") (pinfunction "31_31") (pintype "passive"))
    )
    (net (code "21") (name "/LATCH8") (class "Default")
      (node (ref "LATCH2") (pin "12") (pinfunction "8Q_12") (pintype "tri_state"))
      (node (ref "R44") (pin "2") (pinfunction "2_2") (pintype "passive"))
      (node (ref "U$1") (pin "18") (pinfunction "18_18") (pintype "passive"))
    )
    (net (code "22") (name "/LED_ADM") (class "Default")
      (node (ref "ADM-LED") (pin "3") (pinfunction "3_3") (pintype "passive"))
      (node (ref "R33") (pin "2") (pinfunction "2_2") (pintype "passive"))
    )
    (net (code "23") (name "/REG-P24") (class "Default")
      (node (ref "LATCH2") (pin "11") (pinfunction "C_11") (pintype "input"))
      (node (ref "REGNATIX") (pin "33") (pinfunction "P24_33") (pintype "bidirectional"))
    )
    (net (code "24") (name "/RX") (class "Default")
      (node (ref "PROPPLUG") (pin "2") (pinfunction "2_2") (pintype "passive"))
      (node (ref "S2") (pin "4") (pinfunction "4_4") (pintype "passive"))
      (node (ref "S2") (pin "5") (pinfunction "5_5") (pintype "passive"))
      (node (ref "S2") (pin "6") (pinfunction "6_6") (pintype "passive"))
      (node (ref "U$1") (pin "23") (pinfunction "23_23") (pintype "passive"))
    )
    (net (code "25") (name "/RX-ADM") (class "Default")
      (node (ref "ADMINISTRA") (pin "40") (pinfunction "P31_40") (pintype "bidirectional"))
      (node (ref "S2") (pin "9") (pinfunction "9_9") (pintype "passive"))
    )
    (net (code "26") (name "/RX-BEL") (class "Default")
      (node (ref "BELLATRIX") (pin "40") (pinfunction "P31_40") (pintype "bidirectional"))
      (node (ref "S2") (pin "8") (pinfunction "8_8") (pintype "passive"))
    )
    (net (code "27") (name "/RX-REG") (class "Default")
      (node (ref "IC6") (pin "9") (pinfunction "B_9") (pintype "tri_state"))
      (node (ref "REGNATIX") (pin "40") (pinfunction "P31_40") (pintype "bidirectional"))
      (node (ref "S2") (pin "7") (pinfunction "7_7") (pintype "passive"))
    )
    (net (code "28") (name "/TX") (class "Default")
      (node (ref "PROPPLUG") (pin "1") (pinfunction "1_1") (pintype "passive"))
      (node (ref "S2") (pin "1") (pinfunction "1_1") (pintype "passive"))
      (node (ref "S2") (pin "2") (pinfunction "2_2") (pintype "passive"))
      (node (ref "S2") (pin "3") (pinfunction "3_3") (pintype "passive"))
      (node (ref "U$1") (pin "21") (pinfunction "21_21") (pintype "passive"))
    )
    (net (code "29") (name "/TX-ADM") (class "Default")
      (node (ref "ADMINISTRA") (pin "39") (pinfunction "P30_39") (pintype "bidirectional"))
      (node (ref "S2") (pin "12") (pinfunction "12_12") (pintype "passive"))
    )
    (net (code "30") (name "/TX-BEL") (class "Default")
      (node (ref "BELLATRIX") (pin "39") (pinfunction "P30_39") (pintype "bidirectional"))
      (node (ref "S2") (pin "11") (pinfunction "11_11") (pintype "passive"))
    )
    (net (code "31") (name "/TX-REG") (class "Default")
      (node (ref "IC6") (pin "10") (pinfunction "B_10") (pintype "tri_state"))
      (node (ref "REGNATIX") (pin "39") (pinfunction "P30_39") (pintype "bidirectional"))
      (node (ref "S2") (pin "10") (pinfunction "10_10") (pintype "passive"))
    )
    (net (code "32") (name "/WR") (class "Default")
      (node (ref "ADMINISTRA") (pin "35") (pinfunction "P26_35") (pintype "bidirectional"))
      (node (ref "BELLATRIX") (pin "35") (pinfunction "P26_35") (pintype "bidirectional"))
      (node (ref "IC10") (pin "29") (pinfunction "WE_29") (pintype "input"))
      (node (ref "IC9") (pin "29") (pinfunction "WE_29") (pintype "input"))
      (node (ref "R28") (pin "2") (pinfunction "2_2") (pintype "passive"))
      (node (ref "REGNATIX") (pin "35") (pinfunction "P26_35") (pintype "bidirectional"))
      (node (ref "U$1") (pin "17") (pinfunction "17_17") (pintype "passive"))
    )
    (net (code "33") (name "/{slash}HS") (class "Default")
      (node (ref "D1") (pin "A") (pinfunction "A_A") (pintype "passive"))
      (node (ref "D3") (pin "A") (pinfunction "A_A") (pintype "passive"))
      (node (ref "R27") (pin "2") (pinfunction "2_2") (pintype "passive"))
      (node (ref "REGNATIX") (pin "36") (pinfunction "P27_36") (pintype "bidirectional"))
      (node (ref "U$1") (pin "22") (pinfunction "22_22") (pintype "passive"))
    )
    (net (code "34") (name "GND") (class "Default")
      (node (ref "ADM") (pin "1") (pinfunction "A0_1") (pintype "input"))
      (node (ref "ADM") (pin "3") (pinfunction "A2_3") (pintype "input"))
      (node (ref "ADM") (pin "4") (pinfunction "GND_4") (pintype "power_in"))
      (node (ref "ADM") (pin "7") (pinfunction "WP_7") (pintype "input"))
      (node (ref "ADM-LED") (pin "1") (pinfunction "1_1") (pintype "passive"))
      (node (ref "ADMINISTRA") (pin "10") (pinfunction "BOE/_10") (pintype "input"))
      (node (ref "AUDIO") (pin "1") (pinfunction "1_1") (pintype "passive"))
      (node (ref "BEL") (pin "1") (pinfunction "A0_1") (pintype "input"))
      (node (ref "BEL") (pin "3") (pinfunction "A2_3") (pintype "input"))
      (node (ref "BEL") (pin "4") (pinfunction "GND_4") (pintype "power_in"))
      (node (ref "BEL") (pin "7") (pinfunction "WP_7") (pintype "input"))
      (node (ref "BELLATRIX") (pin "10") (pinfunction "BOE/_10") (pintype "input"))
      (node (ref "C1") (pin "2") (pinfunction "2_2") (pintype "passive"))
      (node (ref "C10") (pin "2") (pinfunction "2_2") (pintype "passive"))
      (node (ref "C11") (pin "2") (pinfunction "2_2") (pintype "passive"))
      (node (ref "C12") (pin "2") (pinfunction "2_2") (pintype "passive"))
      (node (ref "C13") (pin "2") (pinfunction "2_2") (pintype "passive"))
      (node (ref "C14") (pin "2") (pinfunction "2_2") (pintype "passive"))
      (node (ref "C17") (pin "2") (pinfunction "2_2") (pintype "passive"))
      (node (ref "C18") (pin "2") (pinfunction "2_2") (pintype "passive"))
      (node (ref "C19") (pin "2") (pinfunction "2_2") (pintype "passive"))
      (node (ref "C2") (pin "2") (pinfunction "2_2") (pintype "passive"))
      (node (ref "C20") (pin "2") (pinfunction "2_2") (pintype "passive"))
      (node (ref "C21") (pin "2") (pinfunction "2_2") (pintype "passive"))
      (node (ref "C22") (pin "-") (pinfunction "-_-") (pintype "passive"))
      (node (ref "C23") (pin "2") (pinfunction "2_2") (pintype "passive"))
      (node (ref "C24") (pin "-") (pinfunction "-_-") (pintype "passive"))
      (node (ref "C25") (pin "2") (pinfunction "2_2") (pintype "passive"))
      (node (ref "C26") (pin "2") (pinfunction "2_2") (pintype "passive"))
      (node (ref "C27") (pin "2") (pinfunction "2_2") (pintype "passive"))
      (node (ref "C28") (pin "-") (pinfunction "-_-") (pintype "passive"))
      (node (ref "C29") (pin "2") (pinfunction "2_2") (pintype "passive"))
      (node (ref "C3") (pin "2") (pinfunction "2_2") (pintype "passive"))
      (node (ref "C30") (pin "-") (pinfunction "-_-") (pintype "passive"))
      (node (ref "C4") (pin "2") (pinfunction "2_2") (pintype "passive"))
      (node (ref "C5") (pin "2") (pinfunction "2_2") (pintype "passive"))
      (node (ref "C6") (pin "-") (pinfunction "-_-") (pintype "passive"))
      (node (ref "C7") (pin "2") (pinfunction "2_2") (pintype "passive"))
      (node (ref "C8") (pin "2") (pinfunction "2_2") (pintype "passive"))
      (node (ref "C9") (pin "2") (pinfunction "2_2") (pintype "passive"))
      (node (ref "DIAGNOSE") (pin "9") (pinfunction "9_9") (pintype "passive"))
      (node (ref "ERW.INTERN") (pin "1") (pinfunction "1_1") (pintype "passive"))
      (node (ref "IC10") (pin "16") (pinfunction "VSS_16") (pintype "power_in"))
      (node (ref "IC13") (pin "2") (pinfunction "A1_2") (pintype "input"))
      (node (ref "IC13") (pin "3") (pinfunction "A2_3") (pintype "input"))
      (node (ref "IC13") (pin "8") (pinfunction "VSS_8") (pintype "power_in"))
      (node (ref "IC2") (pin "1") (pinfunction "A0_1") (pintype "input"))
      (node (ref "IC2") (pin "2") (pinfunction "A1_2") (pintype "input"))
      (node (ref "IC2") (pin "3") (pinfunction "A2_3") (pintype "input"))
      (node (ref "IC2") (pin "8") (pinfunction "VSS_8") (pintype "power_in"))
      (node (ref "IC3") (pin "5") (pinfunction "G2B_5") (pintype "input"))
      (node (ref "IC4") (pin "1") (pinfunction "OC_1") (pintype "input"))
      (node (ref "IC5") (pin "1") (pinfunction "OC_1") (pintype "input"))
      (node (ref "IC7") (pin "1") (pinfunction "OC_1") (pintype "input"))
      (node (ref "IC8") (pin "16") (pinfunction "VSS_16") (pintype "power_in"))
      (node (ref "IC8") (pin "22") (pinfunction "CE_22") (pintype "input"))
      (node (ref "IC9") (pin "16") (pinfunction "VSS_16") (pintype "power_in"))
      (node (ref "KEY") (pin "3") (pinfunction "3_3") (pintype "passive"))
      (node (ref "KEY") (pin "SH1") (pinfunction "PE1_SH1") (pintype "power_in"))
      (node (ref "KEY") (pin "SH2") (pinfunction "PE2_SH2") (pintype "power_in"))
      (node (ref "KEY") (pin "SH3") (pinfunction "PE3_SH3") (pintype "power_in"))
      (node (ref "LATCH1") (pin "1") (pinfunction "OC_1") (pintype "input"))
      (node (ref "LATCH2") (pin "1") (pinfunction "OC_1") (pintype "input"))
      (node (ref "LP-INTERN") (pin "4") (pinfunction "4_4") (pintype "passive"))
      (node (ref "MICROMITE") (pin "7") (pinfunction "7_7") (pintype "passive"))
      (node (ref "MOUSE") (pin "3") (pinfunction "3_3") (pintype "passive"))
      (node (ref "MOUSE") (pin "SH1") (pinfunction "PE1_SH1") (pintype "power_in"))
      (node (ref "MOUSE") (pin "SH2") (pinfunction "PE2_SH2") (pintype "power_in"))
      (node (ref "MOUSE") (pin "SH3") (pinfunction "PE3_SH3") (pintype "power_in"))
      (node (ref "PLEXBUS") (pin "1") (pinfunction "1_1") (pintype "passive"))
      (node (ref "POWER") (pin "3") (pinfunction "3_3") (pintype "passive"))
      (node (ref "PROPPLUG") (pin "4") (pinfunction "4_4") (pintype "passive"))
      (node (ref "R11") (pin "2") (pinfunction "2_2") (pintype "passive"))
      (node (ref "R2") (pin "2") (pinfunction "2_2") (pintype "passive"))
      (node (ref "R22") (pin "2") (pinfunction "2_2") (pintype "passive"))
      (node (ref "R29") (pin "2") (pinfunction "2_2") (pintype "passive"))
      (node (ref "REG") (pin "1") (pinfunction "A0_1") (pintype "input"))
      (node (ref "REG") (pin "3") (pinfunction "A2_3") (pintype "input"))
      (node (ref "REG") (pin "4") (pinfunction "GND_4") (pintype "power_in"))
      (node (ref "REG") (pin "7") (pinfunction "WP_7") (pintype "input"))
      (node (ref "REGNATIX") (pin "10") (pinfunction "BOE/_10") (pintype "input"))
      (node (ref "RESET") (pin "2") (pinfunction "2_2") (pintype "passive"))
      (node (ref "RTC") (pin "1") (pinfunction "1_1") (pintype "passive"))
      (node (ref "SD-CARD") (pin "1") (pinfunction "1_1") (pintype "passive"))
      (node (ref "TASTATUR") (pin "4") (pinfunction "4_4") (pintype "passive"))
      (node (ref "U$1") (pin "43") (pinfunction "43_43") (pintype "passive"))
      (node (ref "V51") (pin "10") (pinfunction "B_10") (pintype "input"))
      (node (ref "V51") (pin "12") (pinfunction "A_12") (pintype "input"))
      (node (ref "V51") (pin "13") (pinfunction "B_13") (pintype "input"))
      (node (ref "V51") (pin "4") (pinfunction "A_4") (pintype "input"))
      (node (ref "V51") (pin "5") (pinfunction "B_5") (pintype "input"))
      (node (ref "V51") (pin "9") (pinfunction "A_9") (pintype "input"))
      (node (ref "VIDEO") (pin "2") (pinfunction "2_2") (pintype "passive"))
      (node (ref "VIDEO") (pin "2@1") (pinfunction "3_2@1") (pintype "passive"))
      (node (ref "VIDEO") (pin "2@2") (pinfunction "4_2@2") (pintype "passive"))
      (node (ref "X1") (pin "8") (pinfunction "8_8") (pintype "passive"))
      (node (ref "X2") (pin "8") (pinfunction "8_8") (pintype "passive"))
      (node (ref "X5") (pin "10") (pinfunction "10_10") (pintype "passive"))
      (node (ref "X5") (pin "6") (pinfunction "6_6") (pintype "passive"))
      (node (ref "X5") (pin "7") (pinfunction "7_7") (pintype "passive"))
      (node (ref "X5") (pin "8") (pinfunction "8_8") (pintype "passive"))
      (node (ref "X5") (pin "9") (pinfunction "9_9") (pintype "passive"))
      (node (ref "X5") (pin "VSS") (pinfunction "VSS1_VSS") (pintype "passive"))
      (node (ref "X5") (pin "VSS1") (pinfunction "VSS2_VSS1") (pintype "passive"))
    )
    (net (code "35") (name "Net-(ADM-A1)") (class "Default")
      (node (ref "ADM") (pin "2") (pinfunction "A1_2") (pintype "input"))
      (node (ref "R29") (pin "1") (pinfunction "1_1") (pintype "passive"))
      (node (ref "U$1") (pin "35") (pinfunction "35_35") (pintype "passive"))
    )
    (net (code "36") (name "Net-(ADM-SCL)") (class "Default")
      (node (ref "ADM") (pin "6") (pinfunction "SCL_6") (pintype "bidirectional"))
      (node (ref "ADMINISTRA") (pin "37") (pinfunction "P28_37") (pintype "bidirectional"))
      (node (ref "RN3") (pin "6") (pinfunction "6_6") (pintype "passive"))
      (node (ref "RTC") (pin "3") (pinfunction "3_3") (pintype "passive"))
      (node (ref "U$1") (pin "24") (pinfunction "24_24") (pintype "passive"))
    )
    (net (code "37") (name "Net-(ADM-SDA)") (class "Default")
      (node (ref "ADM") (pin "5") (pinfunction "SDA_5") (pintype "bidirectional"))
      (node (ref "ADMINISTRA") (pin "38") (pinfunction "P29_38") (pintype "bidirectional"))
      (node (ref "RN3") (pin "7") (pinfunction "7_7") (pintype "passive"))
      (node (ref "RTC") (pin "2") (pinfunction "2_2") (pintype "passive"))
      (node (ref "U$1") (pin "26") (pinfunction "26_26") (pintype "passive"))
    )
    (net (code "38") (name "Net-(ADMINISTRAB-P0)") (class "Default")
      (node (ref "ADMINISTRA") (pin "1") (pinfunction "P0_1") (pintype "bidirectional"))
      (node (ref "BELLATRIX") (pin "1") (pinfunction "P0_1") (pintype "bidirectional"))
      (node (ref "IC10") (pin "13") (pinfunction "I/O00_13") (pintype "bidirectional"))
      (node (ref "IC4") (pin "3") (pinfunction "1D_3") (pintype "input"))
      (node (ref "IC5") (pin "3") (pinfunction "1D_3") (pintype "input"))
      (node (ref "IC7") (pin "3") (pinfunction "1D_3") (pintype "input"))
      (node (ref "IC8") (pin "13") (pinfunction "I/O00_13") (pintype "bidirectional"))
      (node (ref "IC9") (pin "13") (pinfunction "I/O00_13") (pintype "bidirectional"))
      (node (ref "REGNATIX") (pin "1") (pinfunction "P0_1") (pintype "bidirectional"))
      (node (ref "U$1") (pin "1") (pinfunction "1_1") (pintype "passive"))
    )
    (net (code "39") (name "Net-(ADMINISTRAB-P1)") (class "Default")
      (node (ref "ADMINISTRA") (pin "2") (pinfunction "P1_2") (pintype "bidirectional"))
      (node (ref "BELLATRIX") (pin "2") (pinfunction "P1_2") (pintype "bidirectional"))
      (node (ref "IC10") (pin "14") (pinfunction "I/O01_14") (pintype "bidirectional"))
      (node (ref "IC4") (pin "4") (pinfunction "2D_4") (pintype "input"))
      (node (ref "IC5") (pin "4") (pinfunction "2D_4") (pintype "input"))
      (node (ref "IC7") (pin "4") (pinfunction "2D_4") (pintype "input"))
      (node (ref "IC8") (pin "14") (pinfunction "I/O01_14") (pintype "bidirectional"))
      (node (ref "IC9") (pin "14") (pinfunction "I/O01_14") (pintype "bidirectional"))
      (node (ref "REGNATIX") (pin "2") (pinfunction "P1_2") (pintype "bidirectional"))
      (node (ref "U$1") (pin "3") (pinfunction "3_3") (pintype "passive"))
    )
    (net (code "40") (name "Net-(ADMINISTRAB-P2)") (class "Default")
      (node (ref "ADMINISTRA") (pin "3") (pinfunction "P2_3") (pintype "bidirectional"))
      (node (ref "BELLATRIX") (pin "3") (pinfunction "P2_3") (pintype "bidirectional"))
      (node (ref "IC10") (pin "15") (pinfunction "I/O02_15") (pintype "bidirectional"))
      (node (ref "IC4") (pin "7") (pinfunction "3D_7") (pintype "input"))
      (node (ref "IC5") (pin "7") (pinfunction "3D_7") (pintype "input"))
      (node (ref "IC7") (pin "7") (pinfunction "3D_7") (pintype "input"))
      (node (ref "IC8") (pin "15") (pinfunction "I/O02_15") (pintype "bidirectional"))
      (node (ref "IC9") (pin "15") (pinfunction "I/O02_15") (pintype "bidirectional"))
      (node (ref "REGNATIX") (pin "3") (pinfunction "P2_3") (pintype "bidirectional"))
      (node (ref "U$1") (pin "5") (pinfunction "5_5") (pintype "passive"))
    )
    (net (code "41") (name "Net-(ADMINISTRAB-P3)") (class "Default")
      (node (ref "ADMINISTRA") (pin "4") (pinfunction "P3_4") (pintype "bidirectional"))
      (node (ref "BELLATRIX") (pin "4") (pinfunction "P3_4") (pintype "bidirectional"))
      (node (ref "IC10") (pin "17") (pinfunction "I/O03_17") (pintype "bidirectional"))
      (node (ref "IC4") (pin "8") (pinfunction "4D_8") (pintype "input"))
      (node (ref "IC5") (pin "8") (pinfunction "4D_8") (pintype "input"))
      (node (ref "IC7") (pin "8") (pinfunction "4D_8") (pintype "input"))
      (node (ref "IC8") (pin "17") (pinfunction "I/O03_17") (pintype "bidirectional"))
      (node (ref "IC9") (pin "17") (pinfunction "I/O03_17") (pintype "bidirectional"))
      (node (ref "REGNATIX") (pin "4") (pinfunction "P3_4") (pintype "bidirectional"))
      (node (ref "U$1") (pin "7") (pinfunction "7_7") (pintype "passive"))
    )
    (net (code "42") (name "Net-(ADMINISTRAB-P4)") (class "Default")
      (node (ref "ADMINISTRA") (pin "5") (pinfunction "P4_5") (pintype "bidirectional"))
      (node (ref "BELLATRIX") (pin "5") (pinfunction "P4_5") (pintype "bidirectional"))
      (node (ref "IC10") (pin "18") (pinfunction "I/O04_18") (pintype "bidirectional"))
      (node (ref "IC4") (pin "13") (pinfunction "5D_13") (pintype "input"))
      (node (ref "IC5") (pin "13") (pinfunction "5D_13") (pintype "input"))
      (node (ref "IC7") (pin "13") (pinfunction "5D_13") (pintype "input"))
      (node (ref "IC8") (pin "18") (pinfunction "I/O04_18") (pintype "bidirectional"))
      (node (ref "IC9") (pin "18") (pinfunction "I/O04_18") (pintype "bidirectional"))
      (node (ref "REGNATIX") (pin "5") (pinfunction "P4_5") (pintype "bidirectional"))
      (node (ref "U$1") (pin "9") (pinfunction "9_9") (pintype "passive"))
    )
    (net (code "43") (name "Net-(ADMINISTRAB-P5)") (class "Default")
      (node (ref "ADMINISTRA") (pin "6") (pinfunction "P5_6") (pintype "bidirectional"))
      (node (ref "BELLATRIX") (pin "6") (pinfunction "P5_6") (pintype "bidirectional"))
      (node (ref "IC10") (pin "19") (pinfunction "I/O05_19") (pintype "bidirectional"))
      (node (ref "IC4") (pin "14") (pinfunction "6D_14") (pintype "input"))
      (node (ref "IC5") (pin "14") (pinfunction "6D_14") (pintype "input"))
      (node (ref "IC7") (pin "14") (pinfunction "6D_14") (pintype "input"))
      (node (ref "IC8") (pin "19") (pinfunction "I/O05_19") (pintype "bidirectional"))
      (node (ref "IC9") (pin "19") (pinfunction "I/O05_19") (pintype "bidirectional"))
      (node (ref "REGNATIX") (pin "6") (pinfunction "P5_6") (pintype "bidirectional"))
      (node (ref "U$1") (pin "11") (pinfunction "11_11") (pintype "passive"))
    )
    (net (code "44") (name "Net-(ADMINISTRAB-P6)") (class "Default")
      (node (ref "ADMINISTRA") (pin "7") (pinfunction "P6_7") (pintype "bidirectional"))
      (node (ref "BELLATRIX") (pin "7") (pinfunction "P6_7") (pintype "bidirectional"))
      (node (ref "IC10") (pin "20") (pinfunction "I/O06_20") (pintype "bidirectional"))
      (node (ref "IC4") (pin "17") (pinfunction "7D_17") (pintype "input"))
      (node (ref "IC5") (pin "17") (pinfunction "7D_17") (pintype "input"))
      (node (ref "IC7") (pin "17") (pinfunction "7D_17") (pintype "input"))
      (node (ref "IC8") (pin "20") (pinfunction "I/O06_20") (pintype "bidirectional"))
      (node (ref "IC9") (pin "20") (pinfunction "I/O06_20") (pintype "bidirectional"))
      (node (ref "REGNATIX") (pin "7") (pinfunction "P6_7") (pintype "bidirectional"))
      (node (ref "U$1") (pin "13") (pinfunction "13_13") (pintype "passive"))
    )
    (net (code "45") (name "Net-(ADMINISTRAB-P7)") (class "Default")
      (node (ref "ADMINISTRA") (pin "8") (pinfunction "P7_8") (pintype "bidirectional"))
      (node (ref "BELLATRIX") (pin "8") (pinfunction "P7_8") (pintype "bidirectional"))
      (node (ref "IC10") (pin "21") (pinfunction "I/O07_21") (pintype "bidirectional"))
      (node (ref "IC4") (pin "18") (pinfunction "8D_18") (pintype "input"))
      (node (ref "IC5") (pin "18") (pinfunction "8D_18") (pintype "input"))
      (node (ref "IC7") (pin "18") (pinfunction "8D_18") (pintype "input"))
      (node (ref "IC8") (pin "21") (pinfunction "I/O07_21") (pintype "bidirectional"))
      (node (ref "IC9") (pin "21") (pinfunction "I/O07_21") (pintype "bidirectional"))
      (node (ref "REGNATIX") (pin "8") (pinfunction "P7_8") (pintype "bidirectional"))
      (node (ref "U$1") (pin "15") (pinfunction "15_15") (pintype "passive"))
    )
    (net (code "46") (name "Net-(ADMINISTRAB-P8)") (class "Default")
      (node (ref "ADMINISTRA") (pin "13") (pinfunction "P8_13") (pintype "bidirectional"))
      (node (ref "IC1") (pin "8") (pinfunction "A_8") (pintype "tri_state"))
    )
    (net (code "47") (name "Net-(ADMINISTRAB-P9)") (class "Default")
      (node (ref "ADMINISTRA") (pin "14") (pinfunction "P9_14") (pintype "bidirectional"))
      (node (ref "IC1") (pin "11") (pinfunction "A_11") (pintype "tri_state"))
    )
    (net (code "48") (name "Net-(ADMINISTRAB-P10)") (class "Default")
      (node (ref "ADMINISTRA") (pin "15") (pinfunction "P10_15") (pintype "bidirectional"))
      (node (ref "SD-CARD") (pin "7") (pinfunction "7_7") (pintype "passive"))
    )
    (net (code "49") (name "Net-(ADMINISTRAB-P11)") (class "Default")
      (node (ref "ADMINISTRA") (pin "16") (pinfunction "P11_16") (pintype "bidirectional"))
      (node (ref "SD-CARD") (pin "6") (pinfunction "6_6") (pintype "passive"))
    )
    (net (code "50") (name "Net-(ADMINISTRAB-P12)") (class "Default")
      (node (ref "ADMINISTRA") (pin "17") (pinfunction "P12_17") (pintype "bidirectional"))
      (node (ref "SD-CARD") (pin "5") (pinfunction "5_5") (pintype "passive"))
    )
    (net (code "51") (name "Net-(ADMINISTRAB-P13)") (class "Default")
      (node (ref "ADMINISTRA") (pin "18") (pinfunction "P13_18") (pintype "bidirectional"))
      (node (ref "SD-CARD") (pin "4") (pinfunction "4_4") (pintype "passive"))
    )
    (net (code "52") (name "Net-(ADMINISTRAB-P14)") (class "Default")
      (node (ref "ADMINISTRA") (pin "19") (pinfunction "P14_19") (pintype "bidirectional"))
      (node (ref "U$1") (pin "36") (pinfunction "36_36") (pintype "passive"))
    )
    (net (code "53") (name "Net-(ADMINISTRAB-P15)") (class "Default")
      (node (ref "ADMINISTRA") (pin "20") (pinfunction "P15_20") (pintype "bidirectional"))
      (node (ref "U$1") (pin "38") (pinfunction "38_38") (pintype "passive"))
    )
    (net (code "54") (name "Net-(ADMINISTRAB-P16)") (class "Default")
      (node (ref "ADMINISTRA") (pin "21") (pinfunction "P16_21") (pintype "bidirectional"))
      (node (ref "U$1") (pin "40") (pinfunction "40_40") (pintype "passive"))
    )
    (net (code "55") (name "Net-(ADMINISTRAB-P17)") (class "Default")
      (node (ref "ADMINISTRA") (pin "22") (pinfunction "P17_22") (pintype "bidirectional"))
      (node (ref "U$1") (pin "42") (pinfunction "42_42") (pintype "passive"))
    )
    (net (code "56") (name "Net-(ADMINISTRAB-P18)") (class "Default")
      (node (ref "ADMINISTRA") (pin "23") (pinfunction "P18_23") (pintype "bidirectional"))
      (node (ref "IC13") (pin "14") (pinfunction "SCL_14") (pintype "input"))
      (node (ref "IC2") (pin "14") (pinfunction "SCL_14") (pintype "input"))
      (node (ref "PLEXBUS") (pin "3") (pinfunction "3_3") (pintype "passive"))
      (node (ref "R20") (pin "2") (pinfunction "2_2") (pintype "passive"))
      (node (ref "U$1") (pin "44") (pinfunction "44_44") (pintype "passive"))
    )
    (net (code "57") (name "Net-(ADMINISTRAB-P19)") (class "Default")
      (node (ref "ADMINISTRA") (pin "24") (pinfunction "P19_24") (pintype "bidirectional"))
      (node (ref "IC13") (pin "15") (pinfunction "SDA_15") (pintype "bidirectional"))
      (node (ref "IC2") (pin "15") (pinfunction "SDA_15") (pintype "bidirectional"))
      (node (ref "PLEXBUS") (pin "2") (pinfunction "2_2") (pintype "passive"))
      (node (ref "R21") (pin "2") (pinfunction "2_2") (pintype "passive"))
      (node (ref "U$1") (pin "33") (pinfunction "33_33") (pintype "passive"))
    )
    (net (code "58") (name "Net-(ADMINISTRAB-P20)") (class "Default")
      (node (ref "ADMINISTRA") (pin "25") (pinfunction "P20_25") (pintype "bidirectional"))
      (node (ref "ERW.INTERN") (pin "4") (pinfunction "4_4") (pintype "passive"))
    )
    (net (code "59") (name "Net-(ADMINISTRAB-P21)") (class "Default")
      (node (ref "ADMINISTRA") (pin "26") (pinfunction "P21_26") (pintype "bidirectional"))
      (node (ref "ERW.INTERN") (pin "3") (pinfunction "3_3") (pintype "passive"))
    )
    (net (code "60") (name "Net-(ADMINISTRAB-P22)") (class "Default")
      (node (ref "ADMINISTRA") (pin "27") (pinfunction "P22_27") (pintype "bidirectional"))
      (node (ref "ERW.INTERN") (pin "2") (pinfunction "2_2") (pintype "passive"))
    )
    (net (code "61") (name "Net-(ADMINISTRAB-P23)") (class "Default")
      (node (ref "ADMINISTRA") (pin "28") (pinfunction "P23_28") (pintype "bidirectional"))
      (node (ref "R37") (pin "2") (pinfunction "2_2") (pintype "passive"))
      (node (ref "REGNATIX") (pin "26") (pinfunction "P21_26") (pintype "bidirectional"))
    )
    (net (code "62") (name "Net-(ADMINISTRAB-P24)") (class "Default")
      (node (ref "ADMINISTRA") (pin "33") (pinfunction "P24_33") (pintype "bidirectional"))
      (node (ref "R33") (pin "1") (pinfunction "1_1") (pintype "passive"))
    )
    (net (code "63") (name "Net-(ADMINISTRAB-P27)") (class "Default")
      (node (ref "ADMINISTRA") (pin "36") (pinfunction "P27_36") (pintype "bidirectional"))
      (node (ref "D1") (pin "C") (pinfunction "C_C") (pintype "passive"))
    )
    (net (code "64") (name "Net-(ADMINISTRAB-XI)") (class "Default")
      (node (ref "ADMINISTRA") (pin "30") (pinfunction "XI_30") (pintype "input"))
      (node (ref "Q2") (pin "2") (pinfunction "2_2") (pintype "passive"))
    )
    (net (code "65") (name "Net-(ADMINISTRAB-XO)") (class "Default")
      (node (ref "ADMINISTRA") (pin "31") (pinfunction "XO_31") (pintype "output"))
      (node (ref "Q2") (pin "1") (pinfunction "1_1") (pintype "passive"))
    )
    (net (code "66") (name "Net-(AUDIO-Pad2)") (class "Default")
      (node (ref "AUDIO") (pin "2") (pinfunction "2_2") (pintype "passive"))
      (node (ref "C16") (pin "-") (pinfunction "-_-") (pintype "passive"))
    )
    (net (code "67") (name "Net-(AUDIO-Pad3)") (class "Default")
      (node (ref "AUDIO") (pin "3") (pinfunction "3_3") (pintype "passive"))
      (node (ref "LP-INTERN") (pin "3") (pinfunction "3_3") (pintype "passive"))
    )
    (net (code "68") (name "Net-(AUDIO-Pad4)") (class "Default")
      (node (ref "AUDIO") (pin "4") (pinfunction "4_4") (pintype "passive"))
      (node (ref "LP-INTERN") (pin "2") (pinfunction "2_2") (pintype "passive"))
    )
    (net (code "69") (name "Net-(AUDIO-Pad5)") (class "Default")
      (node (ref "AUDIO") (pin "5") (pinfunction "5_5") (pintype "passive"))
      (node (ref "C15") (pin "-") (pinfunction "-_-") (pintype "passive"))
    )
    (net (code "70") (name "Net-(BEL-A1)") (class "Default")
      (node (ref "BEL") (pin "2") (pinfunction "A1_2") (pintype "input"))
      (node (ref "R22") (pin "1") (pinfunction "1_1") (pintype "passive"))
      (node (ref "U$1") (pin "37") (pinfunction "37_37") (pintype "passive"))
    )
    (net (code "71") (name "Net-(BEL-SCL)") (class "Default")
      (node (ref "BEL") (pin "6") (pinfunction "SCL_6") (pintype "bidirectional"))
      (node (ref "BELLATRIX") (pin "37") (pinfunction "P28_37") (pintype "bidirectional"))
      (node (ref "RN3") (pin "5") (pinfunction "5_5") (pintype "passive"))
      (node (ref "U$1") (pin "28") (pinfunction "28_28") (pintype "passive"))
    )
    (net (code "72") (name "Net-(BEL-SDA)") (class "Default")
      (node (ref "BEL") (pin "5") (pinfunction "SDA_5") (pintype "bidirectional"))
      (node (ref "BELLATRIX") (pin "38") (pinfunction "P29_38") (pintype "bidirectional"))
      (node (ref "RN3") (pin "4") (pinfunction "4_4") (pintype "passive"))
      (node (ref "U$1") (pin "30") (pinfunction "30_30") (pintype "passive"))
    )
    (net (code "73") (name "Net-(BELLATRIXB-P16)") (class "Default")
      (node (ref "BELLATRIX") (pin "21") (pinfunction "P16_21") (pintype "bidirectional"))
      (node (ref "R18") (pin "2") (pinfunction "2_2") (pintype "passive"))
    )
    (net (code "74") (name "Net-(BELLATRIXB-P17)") (class "Default")
      (node (ref "BELLATRIX") (pin "22") (pinfunction "P17_22") (pintype "bidirectional"))
      (node (ref "R19") (pin "2") (pinfunction "2_2") (pintype "passive"))
    )
    (net (code "75") (name "Net-(BELLATRIXB-P18)") (class "Default")
      (node (ref "BELLATRIX") (pin "23") (pinfunction "P18_23") (pintype "bidirectional"))
      (node (ref "IC1") (pin "1") (pinfunction "A_1") (pintype "tri_state"))
      (node (ref "R17") (pin "2") (pinfunction "2_2") (pintype "passive"))
    )
    (net (code "76") (name "Net-(BELLATRIXB-P19)") (class "Default")
      (node (ref "BELLATRIX") (pin "24") (pinfunction "P19_24") (pintype "bidirectional"))
      (node (ref "IC1") (pin "4") (pinfunction "A_4") (pintype "tri_state"))
      (node (ref "R16") (pin "2") (pinfunction "2_2") (pintype "passive"))
    )
    (net (code "77") (name "Net-(BELLATRIXB-P20)") (class "Default")
      (node (ref "BELLATRIX") (pin "25") (pinfunction "P20_25") (pintype "bidirectional"))
      (node (ref "IC3") (pin "1") (pinfunction "A_1") (pintype "input"))
    )
    (net (code "78") (name "Net-(BELLATRIXB-P21)") (class "Default")
      (node (ref "BELLATRIX") (pin "26") (pinfunction "P21_26") (pintype "bidirectional"))
      (node (ref "IC3") (pin "2") (pinfunction "B_2") (pintype "input"))
    )
    (net (code "79") (name "Net-(BELLATRIXB-P22)") (class "Default")
      (node (ref "BELLATRIX") (pin "27") (pinfunction "P22_27") (pintype "bidirectional"))
      (node (ref "IC3") (pin "3") (pinfunction "C_3") (pintype "input"))
    )
    (net (code "80") (name "Net-(BELLATRIXB-P23)") (class "Default")
      (node (ref "BELLATRIX") (pin "28") (pinfunction "P23_28") (pintype "bidirectional"))
      (node (ref "R34") (pin "2") (pinfunction "2_2") (pintype "passive"))
      (node (ref "REGNATIX") (pin "27") (pinfunction "P22_27") (pintype "bidirectional"))
    )
    (net (code "81") (name "Net-(BELLATRIXB-P24)") (class "Default")
      (node (ref "BELLATRIX") (pin "33") (pinfunction "P24_33") (pintype "bidirectional"))
      (node (ref "IC3") (pin "4") (pinfunction "G2A_4") (pintype "input"))
      (node (ref "R30") (pin "1") (pinfunction "1_1") (pintype "passive"))
    )
    (net (code "82") (name "Net-(BELLATRIXB-P27)") (class "Default")
      (node (ref "BELLATRIX") (pin "36") (pinfunction "P27_36") (pintype "bidirectional"))
      (node (ref "D3") (pin "C") (pinfunction "C_C") (pintype "passive"))
    )
    (net (code "83") (name "Net-(BELLATRIXB-XI)") (class "Default")
      (node (ref "BELLATRIX") (pin "30") (pinfunction "XI_30") (pintype "input"))
      (node (ref "Q1") (pin "2") (pinfunction "2_2") (pintype "passive"))
    )
    (net (code "84") (name "Net-(BELLATRIXB-XO)") (class "Default")
      (node (ref "BELLATRIX") (pin "31") (pinfunction "XO_31") (pintype "output"))
      (node (ref "Q1") (pin "1") (pinfunction "1_1") (pintype "passive"))
    )
    (net (code "85") (name "Net-(C13-Pad1)") (class "Default")
      (node (ref "C13") (pin "1") (pinfunction "1_1") (pintype "passive"))
      (node (ref "C15") (pin "+") (pinfunction "+_+") (pintype "passive"))
      (node (ref "R39") (pin "2") (pinfunction "2_2") (pintype "passive"))
    )
    (net (code "86") (name "Net-(C14-Pad1)") (class "Default")
      (node (ref "C14") (pin "1") (pinfunction "1_1") (pintype "passive"))
      (node (ref "C16") (pin "+") (pinfunction "+_+") (pintype "passive"))
      (node (ref "R38") (pin "2") (pinfunction "2_2") (pintype "passive"))
    )
    (net (code "87") (name "Net-(C22-Pad+)") (class "Default")
      (node (ref "C22") (pin "+") (pinfunction "+_+") (pintype "passive"))
      (node (ref "L1") (pin "1") (pinfunction "1_1") (pintype "passive"))
      (node (ref "POWER") (pin "1") (pinfunction "1_1") (pintype "passive"))
    )
    (net (code "88") (name "Net-(C24-Pad+)") (class "Default")
      (node (ref "C24") (pin "+") (pinfunction "+_+") (pintype "passive"))
      (node (ref "L2") (pin "1") (pinfunction "1_1") (pintype "passive"))
      (node (ref "POWER") (pin "2") (pinfunction "2_2") (pintype "passive"))
    )
    (net (code "89") (name "Net-(DIAGNOSE-Pad1)") (class "Default")
      (node (ref "DIAGNOSE") (pin "1") (pinfunction "1_1") (pintype "passive"))
      (node (ref "R25") (pin "1") (pinfunction "1_1") (pintype "passive"))
    )
    (net (code "90") (name "Net-(DIAGNOSE-Pad2)") (class "Default")
      (node (ref "DIAGNOSE") (pin "2") (pinfunction "2_2") (pintype "passive"))
      (node (ref "R42") (pin "1") (pinfunction "1_1") (pintype "passive"))
    )
    (net (code "91") (name "Net-(DIAGNOSE-Pad3)") (class "Default")
      (node (ref "DIAGNOSE") (pin "3") (pinfunction "3_3") (pintype "passive"))
      (node (ref "R43") (pin "1") (pinfunction "1_1") (pintype "passive"))
    )
    (net (code "92") (name "Net-(DIAGNOSE-Pad4)") (class "Default")
      (node (ref "DIAGNOSE") (pin "4") (pinfunction "4_4") (pintype "passive"))
      (node (ref "R45") (pin "1") (pinfunction "1_1") (pintype "passive"))
    )
    (net (code "93") (name "Net-(DIAGNOSE-Pad5)") (class "Default")
      (node (ref "DIAGNOSE") (pin "5") (pinfunction "5_5") (pintype "passive"))
      (node (ref "R1") (pin "1") (pinfunction "1_1") (pintype "passive"))
    )
    (net (code "94") (name "Net-(DIAGNOSE-Pad6)") (class "Default")
      (node (ref "DIAGNOSE") (pin "6") (pinfunction "6_6") (pintype "passive"))
      (node (ref "R40") (pin "1") (pinfunction "1_1") (pintype "passive"))
    )
    (net (code "95") (name "Net-(DIAGNOSE-Pad7)") (class "Default")
      (node (ref "DIAGNOSE") (pin "7") (pinfunction "7_7") (pintype "passive"))
      (node (ref "R41") (pin "1") (pinfunction "1_1") (pintype "passive"))
    )
    (net (code "96") (name "Net-(DIAGNOSE-Pad8)") (class "Default")
      (node (ref "DIAGNOSE") (pin "8") (pinfunction "8_8") (pintype "passive"))
      (node (ref "R44") (pin "1") (pinfunction "1_1") (pintype "passive"))
    )
    (net (code "97") (name "Net-(IC1A-B)") (class "Default")
      (node (ref "IC1") (pin "2") (pinfunction "B_2") (pintype "tri_state"))
      (node (ref "IC1") (pin "9") (pinfunction "B_9") (pintype "tri_state"))
      (node (ref "R39") (pin "1") (pinfunction "1_1") (pintype "passive"))
    )
    (net (code "98") (name "Net-(IC1B-B)") (class "Default")
      (node (ref "IC1") (pin "10") (pinfunction "B_10") (pintype "tri_state"))
      (node (ref "IC1") (pin "3") (pinfunction "B_3") (pintype "tri_state"))
      (node (ref "R38") (pin "1") (pinfunction "1_1") (pintype "passive"))
    )
    (net (code "99") (name "Net-(IC1C-C)") (class "Default")
      (node (ref "IC1") (pin "12") (pinfunction "C_12") (pintype "input"))
      (node (ref "IC1") (pin "6") (pinfunction "C_6") (pintype "input"))
      (node (ref "V51") (pin "3") (pinfunction "Y_3") (pintype "output"))
    )
    (net (code "100") (name "Net-(IC2-P0)") (class "Default")
      (node (ref "IC2") (pin "4") (pinfunction "P0_4") (pintype "bidirectional"))
      (node (ref "RN2") (pin "2") (pinfunction "2_2") (pintype "passive"))
      (node (ref "X1") (pin "1") (pinfunction "1_1") (pintype "passive"))
    )
    (net (code "101") (name "Net-(IC2-P1)") (class "Default")
      (node (ref "IC2") (pin "5") (pinfunction "P1_5") (pintype "bidirectional"))
      (node (ref "RN2") (pin "3") (pinfunction "3_3") (pintype "passive"))
      (node (ref "X1") (pin "2") (pinfunction "2_2") (pintype "passive"))
    )
    (net (code "102") (name "Net-(IC2-P2)") (class "Default")
      (node (ref "IC2") (pin "6") (pinfunction "P2_6") (pintype "bidirectional"))
      (node (ref "RN2") (pin "4") (pinfunction "4_4") (pintype "passive"))
      (node (ref "X1") (pin "3") (pinfunction "3_3") (pintype "passive"))
    )
    (net (code "103") (name "Net-(IC2-P3)") (class "Default")
      (node (ref "IC2") (pin "7") (pinfunction "P3_7") (pintype "bidirectional"))
      (node (ref "RN2") (pin "5") (pinfunction "5_5") (pintype "passive"))
      (node (ref "X1") (pin "4") (pinfunction "4_4") (pintype "passive"))
    )
    (net (code "104") (name "Net-(IC2-P4)") (class "Default")
      (node (ref "IC2") (pin "9") (pinfunction "P4_9") (pintype "bidirectional"))
      (node (ref "RN2") (pin "6") (pinfunction "6_6") (pintype "passive"))
      (node (ref "X1") (pin "6") (pinfunction "6_6") (pintype "passive"))
    )
    (net (code "105") (name "Net-(IC2-P5)") (class "Default")
      (node (ref "IC2") (pin "10") (pinfunction "P5_10") (pintype "bidirectional"))
      (node (ref "RN2") (pin "7") (pinfunction "7_7") (pintype "passive"))
      (node (ref "X1") (pin "5") (pinfunction "5_5") (pintype "passive"))
    )
    (net (code "106") (name "Net-(IC2-P6)") (class "Default")
      (node (ref "IC2") (pin "11") (pinfunction "P6_11") (pintype "bidirectional"))
      (node (ref "RN2") (pin "8") (pinfunction "8_8") (pintype "passive"))
      (node (ref "X1") (pin "9") (pinfunction "9_9") (pintype "passive"))
    )
    (net (code "107") (name "Net-(IC2-P7)") (class "Default")
      (node (ref "IC2") (pin "12") (pinfunction "P7_12") (pintype "bidirectional"))
      (node (ref "JP3") (pin "3") (pinfunction "3_3") (pintype "passive"))
      (node (ref "RN2") (pin "9") (pinfunction "9_9") (pintype "passive"))
    )
    (net (code "108") (name "Net-(IC3A-Y0)") (class "Default")
      (node (ref "IC3") (pin "15") (pinfunction "Y0_15") (pintype "output"))
      (node (ref "IC8") (pin "24") (pinfunction "OE_24") (pintype "input"))
    )
    (net (code "109") (name "Net-(IC3A-Y1)") (class "Default")
      (node (ref "IC3") (pin "14") (pinfunction "Y1_14") (pintype "output"))
      (node (ref "IC8") (pin "29") (pinfunction "WE_29") (pintype "input"))
    )
    (net (code "110") (name "Net-(IC4A-1Q)") (class "Default")
      (node (ref "IC4") (pin "2") (pinfunction "1Q_2") (pintype "tri_state"))
      (node (ref "IC8") (pin "12") (pinfunction "A0_12") (pintype "input"))
    )
    (net (code "111") (name "Net-(IC4A-2Q)") (class "Default")
      (node (ref "IC4") (pin "5") (pinfunction "2Q_5") (pintype "tri_state"))
      (node (ref "IC8") (pin "11") (pinfunction "A1_11") (pintype "input"))
    )
    (net (code "112") (name "Net-(IC4A-3Q)") (class "Default")
      (node (ref "IC4") (pin "6") (pinfunction "3Q_6") (pintype "tri_state"))
      (node (ref "IC8") (pin "10") (pinfunction "A2_10") (pintype "input"))
    )
    (net (code "113") (name "Net-(IC4A-4Q)") (class "Default")
      (node (ref "IC4") (pin "9") (pinfunction "4Q_9") (pintype "tri_state"))
      (node (ref "IC8") (pin "9") (pinfunction "A3_9") (pintype "input"))
    )
    (net (code "114") (name "Net-(IC4A-5Q)") (class "Default")
      (node (ref "IC4") (pin "12") (pinfunction "5Q_12") (pintype "tri_state"))
      (node (ref "IC8") (pin "8") (pinfunction "A4_8") (pintype "input"))
    )
    (net (code "115") (name "Net-(IC4A-6Q)") (class "Default")
      (node (ref "IC4") (pin "15") (pinfunction "6Q_15") (pintype "tri_state"))
      (node (ref "IC8") (pin "7") (pinfunction "A5_7") (pintype "input"))
    )
    (net (code "116") (name "Net-(IC4A-7Q)") (class "Default")
      (node (ref "IC4") (pin "16") (pinfunction "7Q_16") (pintype "tri_state"))
      (node (ref "IC8") (pin "6") (pinfunction "A6_6") (pintype "input"))
    )
    (net (code "117") (name "Net-(IC4A-8Q)") (class "Default")
      (node (ref "IC4") (pin "19") (pinfunction "8Q_19") (pintype "tri_state"))
      (node (ref "IC8") (pin "5") (pinfunction "A7_5") (pintype "input"))
    )
    (net (code "118") (name "Net-(IC5A-1Q)") (class "Default")
      (node (ref "IC5") (pin "2") (pinfunction "1Q_2") (pintype "tri_state"))
      (node (ref "IC8") (pin "27") (pinfunction "A8_27") (pintype "input"))
    )
    (net (code "119") (name "Net-(IC5A-2Q)") (class "Default")
      (node (ref "IC5") (pin "5") (pinfunction "2Q_5") (pintype "tri_state"))
      (node (ref "IC8") (pin "26") (pinfunction "A9_26") (pintype "input"))
    )
    (net (code "120") (name "Net-(IC5A-3Q)") (class "Default")
      (node (ref "IC5") (pin "6") (pinfunction "3Q_6") (pintype "tri_state"))
      (node (ref "IC8") (pin "23") (pinfunction "A10_23") (pintype "input"))
    )
    (net (code "121") (name "Net-(IC5A-4Q)") (class "Default")
      (node (ref "IC5") (pin "9") (pinfunction "4Q_9") (pintype "tri_state"))
      (node (ref "IC8") (pin "25") (pinfunction "A11_25") (pintype "input"))
    )
    (net (code "122") (name "Net-(IC5A-5Q)") (class "Default")
      (node (ref "IC5") (pin "12") (pinfunction "5Q_12") (pintype "tri_state"))
      (node (ref "IC8") (pin "4") (pinfunction "A12_4") (pintype "input"))
    )
    (net (code "123") (name "Net-(IC5A-6Q)") (class "Default")
      (node (ref "IC5") (pin "15") (pinfunction "6Q_15") (pintype "tri_state"))
      (node (ref "IC8") (pin "28") (pinfunction "A13_28") (pintype "input"))
    )
    (net (code "124") (name "Net-(IC5A-7Q)") (class "Default")
      (node (ref "IC5") (pin "16") (pinfunction "7Q_16") (pintype "tri_state"))
      (node (ref "IC8") (pin "3") (pinfunction "A14_3") (pintype "input"))
    )
    (net (code "125") (name "Net-(IC5A-8Q)") (class "Default")
      (node (ref "IC5") (pin "19") (pinfunction "8Q_19") (pintype "tri_state"))
      (node (ref "IC8") (pin "31") (pinfunction "A15_31") (pintype "input"))
    )
    (net (code "126") (name "Net-(IC6C-A)") (class "Default")
      (node (ref "IC6") (pin "8") (pinfunction "A_8") (pintype "tri_state"))
      (node (ref "MICROMITE") (pin "2") (pinfunction "2_2") (pintype "passive"))
    )
    (net (code "127") (name "Net-(IC6D-A)") (class "Default")
      (node (ref "IC6") (pin "11") (pinfunction "A_11") (pintype "tri_state"))
      (node (ref "MICROMITE") (pin "1") (pinfunction "1_1") (pintype "passive"))
    )
    (net (code "128") (name "Net-(IC7A-1Q)") (class "Default")
      (node (ref "IC7") (pin "2") (pinfunction "1Q_2") (pintype "tri_state"))
      (node (ref "IC8") (pin "2") (pinfunction "A16_2") (pintype "input"))
    )
    (net (code "129") (name "Net-(IC7A-2Q)") (class "Default")
      (node (ref "IC7") (pin "5") (pinfunction "2Q_5") (pintype "tri_state"))
      (node (ref "IC8") (pin "30") (pinfunction "A17_30") (pintype "input"))
    )
    (net (code "130") (name "Net-(IC7A-3Q)") (class "Default")
      (node (ref "IC7") (pin "6") (pinfunction "3Q_6") (pintype "tri_state"))
      (node (ref "IC8") (pin "1") (pinfunction "A18_1") (pintype "input"))
    )
    (net (code "131") (name "Net-(IC9-CE)") (class "Default")
      (node (ref "IC9") (pin "22") (pinfunction "CE_22") (pintype "input"))
      (node (ref "IC9") (pin "24") (pinfunction "OE_24") (pintype "input"))
      (node (ref "R36") (pin "2") (pinfunction "2_2") (pintype "passive"))
      (node (ref "REGNATIX") (pin "25") (pinfunction "P20_25") (pintype "bidirectional"))
    )
    (net (code "132") (name "Net-(IC10-A0)") (class "Default")
      (node (ref "IC10") (pin "12") (pinfunction "A0_12") (pintype "input"))
      (node (ref "IC9") (pin "12") (pinfunction "A0_12") (pintype "input"))
      (node (ref "LATCH1") (pin "2") (pinfunction "1D_2") (pintype "input"))
      (node (ref "LATCH2") (pin "2") (pinfunction "1D_2") (pintype "input"))
      (node (ref "REGNATIX") (pin "13") (pinfunction "P8_13") (pintype "bidirectional"))
    )
    (net (code "133") (name "Net-(IC10-A1)") (class "Default")
      (node (ref "IC10") (pin "11") (pinfunction "A1_11") (pintype "input"))
      (node (ref "IC9") (pin "11") (pinfunction "A1_11") (pintype "input"))
      (node (ref "LATCH1") (pin "3") (pinfunction "2D_3") (pintype "input"))
      (node (ref "LATCH2") (pin "3") (pinfunction "2D_3") (pintype "input"))
      (node (ref "REGNATIX") (pin "14") (pinfunction "P9_14") (pintype "bidirectional"))
    )
    (net (code "134") (name "Net-(IC10-A2)") (class "Default")
      (node (ref "IC10") (pin "10") (pinfunction "A2_10") (pintype "input"))
      (node (ref "IC9") (pin "10") (pinfunction "A2_10") (pintype "input"))
      (node (ref "LATCH1") (pin "4") (pinfunction "3D_4") (pintype "input"))
      (node (ref "LATCH2") (pin "4") (pinfunction "3D_4") (pintype "input"))
      (node (ref "REGNATIX") (pin "15") (pinfunction "P10_15") (pintype "bidirectional"))
    )
    (net (code "135") (name "Net-(IC10-A3)") (class "Default")
      (node (ref "IC10") (pin "9") (pinfunction "A3_9") (pintype "input"))
      (node (ref "IC9") (pin "9") (pinfunction "A3_9") (pintype "input"))
      (node (ref "LATCH1") (pin "5") (pinfunction "4D_5") (pintype "input"))
      (node (ref "LATCH2") (pin "5") (pinfunction "4D_5") (pintype "input"))
      (node (ref "REGNATIX") (pin "16") (pinfunction "P11_16") (pintype "bidirectional"))
    )
    (net (code "136") (name "Net-(IC10-A4)") (class "Default")
      (node (ref "IC10") (pin "8") (pinfunction "A4_8") (pintype "input"))
      (node (ref "IC9") (pin "8") (pinfunction "A4_8") (pintype "input"))
      (node (ref "LATCH1") (pin "6") (pinfunction "5D_6") (pintype "input"))
      (node (ref "LATCH2") (pin "6") (pinfunction "5D_6") (pintype "input"))
      (node (ref "REGNATIX") (pin "17") (pinfunction "P12_17") (pintype "bidirectional"))
    )
    (net (code "137") (name "Net-(IC10-A5)") (class "Default")
      (node (ref "IC10") (pin "7") (pinfunction "A5_7") (pintype "input"))
      (node (ref "IC9") (pin "7") (pinfunction "A5_7") (pintype "input"))
      (node (ref "LATCH1") (pin "7") (pinfunction "6D_7") (pintype "input"))
      (node (ref "LATCH2") (pin "7") (pinfunction "6D_7") (pintype "input"))
      (node (ref "REGNATIX") (pin "18") (pinfunction "P13_18") (pintype "bidirectional"))
    )
    (net (code "138") (name "Net-(IC10-A6)") (class "Default")
      (node (ref "IC10") (pin "6") (pinfunction "A6_6") (pintype "input"))
      (node (ref "IC9") (pin "6") (pinfunction "A6_6") (pintype "input"))
      (node (ref "LATCH1") (pin "8") (pinfunction "7D_8") (pintype "input"))
      (node (ref "LATCH2") (pin "8") (pinfunction "7D_8") (pintype "input"))
      (node (ref "REGNATIX") (pin "19") (pinfunction "P14_19") (pintype "bidirectional"))
    )
    (net (code "139") (name "Net-(IC10-A7)") (class "Default")
      (node (ref "IC10") (pin "5") (pinfunction "A7_5") (pintype "input"))
      (node (ref "IC9") (pin "5") (pinfunction "A7_5") (pintype "input"))
      (node (ref "LATCH1") (pin "9") (pinfunction "8D_9") (pintype "input"))
      (node (ref "LATCH2") (pin "9") (pinfunction "8D_9") (pintype "input"))
      (node (ref "REGNATIX") (pin "20") (pinfunction "P15_20") (pintype "bidirectional"))
    )
    (net (code "140") (name "Net-(IC10-A8)") (class "Default")
      (node (ref "IC10") (pin "27") (pinfunction "A8_27") (pintype "input"))
      (node (ref "IC9") (pin "27") (pinfunction "A8_27") (pintype "input"))
      (node (ref "REGNATIX") (pin "23") (pinfunction "P18_23") (pintype "bidirectional"))
    )
    (net (code "141") (name "Net-(IC10-A9)") (class "Default")
      (node (ref "IC10") (pin "26") (pinfunction "A9_26") (pintype "input"))
      (node (ref "IC9") (pin "26") (pinfunction "A9_26") (pintype "input"))
      (node (ref "REGNATIX") (pin "22") (pinfunction "P17_22") (pintype "bidirectional"))
    )
    (net (code "142") (name "Net-(IC10-A10)") (class "Default")
      (node (ref "IC10") (pin "23") (pinfunction "A10_23") (pintype "input"))
      (node (ref "IC9") (pin "23") (pinfunction "A10_23") (pintype "input"))
      (node (ref "REGNATIX") (pin "21") (pinfunction "P16_21") (pintype "bidirectional"))
    )
    (net (code "143") (name "Net-(IC10-A11)") (class "Default")
      (node (ref "IC10") (pin "25") (pinfunction "A11_25") (pintype "input"))
      (node (ref "IC9") (pin "25") (pinfunction "A11_25") (pintype "input"))
      (node (ref "LATCH1") (pin "19") (pinfunction "1Q_19") (pintype "tri_state"))
    )
    (net (code "144") (name "Net-(IC10-A12)") (class "Default")
      (node (ref "IC10") (pin "4") (pinfunction "A12_4") (pintype "input"))
      (node (ref "IC9") (pin "4") (pinfunction "A12_4") (pintype "input"))
      (node (ref "LATCH1") (pin "18") (pinfunction "2Q_18") (pintype "tri_state"))
    )
    (net (code "145") (name "Net-(IC10-A13)") (class "Default")
      (node (ref "IC10") (pin "28") (pinfunction "A13_28") (pintype "input"))
      (node (ref "IC9") (pin "28") (pinfunction "A13_28") (pintype "input"))
      (node (ref "LATCH1") (pin "17") (pinfunction "3Q_17") (pintype "tri_state"))
    )
    (net (code "146") (name "Net-(IC10-A14)") (class "Default")
      (node (ref "IC10") (pin "3") (pinfunction "A14_3") (pintype "input"))
      (node (ref "IC9") (pin "3") (pinfunction "A14_3") (pintype "input"))
      (node (ref "LATCH1") (pin "16") (pinfunction "4Q_16") (pintype "tri_state"))
    )
    (net (code "147") (name "Net-(IC10-A15)") (class "Default")
      (node (ref "IC10") (pin "31") (pinfunction "A15_31") (pintype "input"))
      (node (ref "IC9") (pin "31") (pinfunction "A15_31") (pintype "input"))
      (node (ref "LATCH1") (pin "15") (pinfunction "5Q_15") (pintype "tri_state"))
    )
    (net (code "148") (name "Net-(IC10-A16)") (class "Default")
      (node (ref "IC10") (pin "2") (pinfunction "A16_2") (pintype "input"))
      (node (ref "IC9") (pin "2") (pinfunction "A16_2") (pintype "input"))
      (node (ref "LATCH1") (pin "14") (pinfunction "6Q_14") (pintype "tri_state"))
    )
    (net (code "149") (name "Net-(IC10-A17)") (class "Default")
      (node (ref "IC10") (pin "30") (pinfunction "A17_30") (pintype "input"))
      (node (ref "IC9") (pin "30") (pinfunction "A17_30") (pintype "input"))
      (node (ref "LATCH1") (pin "13") (pinfunction "7Q_13") (pintype "tri_state"))
    )
    (net (code "150") (name "Net-(IC10-A18)") (class "Default")
      (node (ref "IC10") (pin "1") (pinfunction "A18_1") (pintype "input"))
      (node (ref "IC9") (pin "1") (pinfunction "A18_1") (pintype "input"))
      (node (ref "LATCH1") (pin "12") (pinfunction "8Q_12") (pintype "tri_state"))
    )
    (net (code "151") (name "Net-(IC10-CE)") (class "Default")
      (node (ref "IC10") (pin "22") (pinfunction "CE_22") (pintype "input"))
      (node (ref "IC10") (pin "24") (pinfunction "OE_24") (pintype "input"))
      (node (ref "R35") (pin "2") (pinfunction "2_2") (pintype "passive"))
      (node (ref "REGNATIX") (pin "24") (pinfunction "P19_24") (pintype "bidirectional"))
    )
    (net (code "152") (name "Net-(IC12A-Y1)") (class "Default")
      (node (ref "IC12") (pin "18") (pinfunction "Y1_18") (pintype "tri_state"))
      (node (ref "R8") (pin "2") (pinfunction "2_2") (pintype "passive"))
    )
    (net (code "153") (name "Net-(IC12A-Y2)") (class "Default")
      (node (ref "IC12") (pin "16") (pinfunction "Y2_16") (pintype "tri_state"))
      (node (ref "R7") (pin "2") (pinfunction "2_2") (pintype "passive"))
    )
    (net (code "154") (name "Net-(IC12A-Y3)") (class "Default")
      (node (ref "IC12") (pin "14") (pinfunction "Y3_14") (pintype "tri_state"))
      (node (ref "R6") (pin "2") (pinfunction "2_2") (pintype "passive"))
    )
    (net (code "155") (name "Net-(IC12A-Y4)") (class "Default")
      (node (ref "IC12") (pin "12") (pinfunction "Y4_12") (pintype "tri_state"))
      (node (ref "R5") (pin "2") (pinfunction "2_2") (pintype "passive"))
    )
    (net (code "156") (name "Net-(IC12B-Y1)") (class "Default")
      (node (ref "IC12") (pin "9") (pinfunction "Y1_9") (pintype "tri_state"))
      (node (ref "R23") (pin "2") (pinfunction "2_2") (pintype "passive"))
      (node (ref "R4") (pin "2") (pinfunction "2_2") (pintype "passive"))
    )
    (net (code "157") (name "Net-(IC12B-Y2)") (class "Default")
      (node (ref "IC12") (pin "7") (pinfunction "Y2_7") (pintype "tri_state"))
      (node (ref "R24") (pin "2") (pinfunction "2_2") (pintype "passive"))
      (node (ref "R3") (pin "2") (pinfunction "2_2") (pintype "passive"))
    )
    (net (code "158") (name "Net-(IC12B-Y3)") (class "Default")
      (node (ref "IC12") (pin "5") (pinfunction "Y3_5") (pintype "tri_state"))
      (node (ref "R10") (pin "2") (pinfunction "2_2") (pintype "passive"))
      (node (ref "R26") (pin "2") (pinfunction "2_2") (pintype "passive"))
    )
    (net (code "159") (name "Net-(IC12B-Y4)") (class "Default")
      (node (ref "IC12") (pin "3") (pinfunction "Y4_3") (pintype "tri_state"))
      (node (ref "R9") (pin "2") (pinfunction "2_2") (pintype "passive"))
    )
    (net (code "160") (name "Net-(IC13-P0)") (class "Default")
      (node (ref "IC13") (pin "4") (pinfunction "P0_4") (pintype "bidirectional"))
      (node (ref "RN4") (pin "2") (pinfunction "2_2") (pintype "passive"))
      (node (ref "X2") (pin "1") (pinfunction "1_1") (pintype "passive"))
    )
    (net (code "161") (name "Net-(IC13-P1)") (class "Default")
      (node (ref "IC13") (pin "5") (pinfunction "P1_5") (pintype "bidirectional"))
      (node (ref "RN4") (pin "3") (pinfunction "3_3") (pintype "passive"))
      (node (ref "X2") (pin "2") (pinfunction "2_2") (pintype "passive"))
    )
    (net (code "162") (name "Net-(IC13-P2)") (class "Default")
      (node (ref "IC13") (pin "6") (pinfunction "P2_6") (pintype "bidirectional"))
      (node (ref "RN4") (pin "4") (pinfunction "4_4") (pintype "passive"))
      (node (ref "X2") (pin "3") (pinfunction "3_3") (pintype "passive"))
    )
    (net (code "163") (name "Net-(IC13-P3)") (class "Default")
      (node (ref "IC13") (pin "7") (pinfunction "P3_7") (pintype "bidirectional"))
      (node (ref "RN4") (pin "5") (pinfunction "5_5") (pintype "passive"))
      (node (ref "X2") (pin "4") (pinfunction "4_4") (pintype "passive"))
    )
    (net (code "164") (name "Net-(IC13-P4)") (class "Default")
      (node (ref "IC13") (pin "9") (pinfunction "P4_9") (pintype "bidirectional"))
      (node (ref "RN4") (pin "6") (pinfunction "6_6") (pintype "passive"))
      (node (ref "X2") (pin "6") (pinfunction "6_6") (pintype "passive"))
    )
    (net (code "165") (name "Net-(IC13-P5)") (class "Default")
      (node (ref "IC13") (pin "10") (pinfunction "P5_10") (pintype "bidirectional"))
      (node (ref "RN4") (pin "7") (pinfunction "7_7") (pintype "passive"))
      (node (ref "X2") (pin "5") (pinfunction "5_5") (pintype "passive"))
    )
    (net (code "166") (name "Net-(IC13-P6)") (class "Default")
      (node (ref "IC13") (pin "11") (pinfunction "P6_11") (pintype "bidirectional"))
      (node (ref "RN4") (pin "8") (pinfunction "8_8") (pintype "passive"))
      (node (ref "X2") (pin "9") (pinfunction "9_9") (pintype "passive"))
    )
    (net (code "167") (name "Net-(IC13-P7)") (class "Default")
      (node (ref "IC13") (pin "12") (pinfunction "P7_12") (pintype "bidirectional"))
      (node (ref "JP2") (pin "3") (pinfunction "3_3") (pintype "passive"))
      (node (ref "RN4") (pin "9") (pinfunction "9_9") (pintype "passive"))
    )
    (net (code "168") (name "Net-(JP2-Pad2)") (class "Default")
      (node (ref "JP2") (pin "2") (pinfunction "2_2") (pintype "passive"))
      (node (ref "X2") (pin "7") (pinfunction "7_7") (pintype "passive"))
    )
    (net (code "169") (name "Net-(JP3-Pad2)") (class "Default")
      (node (ref "JP3") (pin "2") (pinfunction "2_2") (pintype "passive"))
      (node (ref "X1") (pin "7") (pinfunction "7_7") (pintype "passive"))
    )
    (net (code "170") (name "Net-(KEY-Pad1)") (class "Default")
      (node (ref "KEY") (pin "1") (pinfunction "1_1") (pintype "passive"))
      (node (ref "R15") (pin "1") (pinfunction "1_1") (pintype "passive"))
      (node (ref "R19") (pin "1") (pinfunction "1_1") (pintype "passive"))
      (node (ref "TASTATUR") (pin "2") (pinfunction "2_2") (pintype "passive"))
    )
    (net (code "171") (name "Net-(KEY-Pad6)") (class "Default")
      (node (ref "KEY") (pin "6") (pinfunction "6_6") (pintype "passive"))
      (node (ref "R14") (pin "1") (pinfunction "1_1") (pintype "passive"))
      (node (ref "R18") (pin "1") (pinfunction "1_1") (pintype "passive"))
      (node (ref "TASTATUR") (pin "3") (pinfunction "3_3") (pintype "passive"))
    )
    (net (code "172") (name "Net-(LATCH1A-C)") (class "Default")
      (node (ref "LATCH1") (pin "11") (pinfunction "C_11") (pintype "input"))
      (node (ref "REGNATIX") (pin "28") (pinfunction "P23_28") (pintype "bidirectional"))
    )
    (net (code "173") (name "Net-(MOUSE-Pad1)") (class "Default")
      (node (ref "MOUSE") (pin "1") (pinfunction "1_1") (pintype "passive"))
      (node (ref "R13") (pin "1") (pinfunction "1_1") (pintype "passive"))
      (node (ref "R16") (pin "1") (pinfunction "1_1") (pintype "passive"))
    )
    (net (code "174") (name "Net-(MOUSE-Pad6)") (class "Default")
      (node (ref "MOUSE") (pin "6") (pinfunction "6_6") (pintype "passive"))
      (node (ref "R12") (pin "1") (pinfunction "1_1") (pintype "passive"))
      (node (ref "R17") (pin "1") (pinfunction "1_1") (pintype "passive"))
    )
    (net (code "175") (name "Net-(R3-Pad1)") (class "Default")
      (node (ref "R3") (pin "1") (pinfunction "1_1") (pintype "passive"))
      (node (ref "X5") (pin "13") (pinfunction "13_13") (pintype "passive"))
    )
    (net (code "176") (name "Net-(R4-Pad1)") (class "Default")
      (node (ref "R4") (pin "1") (pinfunction "1_1") (pintype "passive"))
      (node (ref "X5") (pin "14") (pinfunction "14_14") (pintype "passive"))
    )
    (net (code "177") (name "Net-(R5-Pad1)") (class "Default")
      (node (ref "R5") (pin "1") (pinfunction "1_1") (pintype "passive"))
      (node (ref "R6") (pin "1") (pinfunction "1_1") (pintype "passive"))
      (node (ref "X5") (pin "1") (pinfunction "1_1") (pintype "passive"))
    )
    (net (code "178") (name "Net-(R7-Pad1)") (class "Default")
      (node (ref "R7") (pin "1") (pinfunction "1_1") (pintype "passive"))
      (node (ref "R8") (pin "1") (pinfunction "1_1") (pintype "passive"))
      (node (ref "X5") (pin "2") (pinfunction "2_2") (pintype "passive"))
    )
    (net (code "179") (name "Net-(R10-Pad1)") (class "Default")
      (node (ref "R10") (pin "1") (pinfunction "1_1") (pintype "passive"))
      (node (ref "R9") (pin "1") (pinfunction "1_1") (pintype "passive"))
      (node (ref "X5") (pin "3") (pinfunction "3_3") (pintype "passive"))
    )
    (net (code "180") (name "Net-(R23-Pad1)") (class "Default")
      (node (ref "R23") (pin "1") (pinfunction "1_1") (pintype "passive"))
      (node (ref "R24") (pin "1") (pinfunction "1_1") (pintype "passive"))
      (node (ref "R26") (pin "1") (pinfunction "1_1") (pintype "passive"))
      (node (ref "VIDEO") (pin "1") (pinfunction "1_1") (pintype "passive"))
    )
    (net (code "181") (name "Net-(REG-A1)") (class "Default")
      (node (ref "R2") (pin "1") (pinfunction "1_1") (pintype "passive"))
      (node (ref "REG") (pin "2") (pinfunction "A1_2") (pintype "input"))
      (node (ref "U$1") (pin "39") (pinfunction "39_39") (pintype "passive"))
    )
    (net (code "182") (name "Net-(REG-SCL)") (class "Default")
      (node (ref "MICROMITE") (pin "3") (pinfunction "3_3") (pintype "passive"))
      (node (ref "REG") (pin "6") (pinfunction "SCL_6") (pintype "bidirectional"))
      (node (ref "REGNATIX") (pin "37") (pinfunction "P28_37") (pintype "bidirectional"))
      (node (ref "RN3") (pin "3") (pinfunction "3_3") (pintype "passive"))
      (node (ref "U$1") (pin "32") (pinfunction "32_32") (pintype "passive"))
    )
    (net (code "183") (name "Net-(REG-SDA)") (class "Default")
      (node (ref "MICROMITE") (pin "4") (pinfunction "4_4") (pintype "passive"))
      (node (ref "REG") (pin "5") (pinfunction "SDA_5") (pintype "bidirectional"))
      (node (ref "REGNATIX") (pin "38") (pinfunction "P29_38") (pintype "bidirectional"))
      (node (ref "RN3") (pin "2") (pinfunction "2_2") (pintype "passive"))
      (node (ref "U$1") (pin "34") (pinfunction "34_34") (pintype "passive"))
    )
    (net (code "184") (name "Net-(REGNATIXB-XI)") (class "Default")
      (node (ref "Q3") (pin "1") (pinfunction "1_1") (pintype "passive"))
      (node (ref "REGNATIX") (pin "30") (pinfunction "XI_30") (pintype "input"))
    )
    (net (code "185") (name "Net-(REGNATIXB-XO)") (class "Default")
      (node (ref "Q3") (pin "2") (pinfunction "2_2") (pintype "passive"))
      (node (ref "REGNATIX") (pin "31") (pinfunction "XO_31") (pintype "output"))
    )
    (net (code "186") (name "VCC") (class "Default")
      (node (ref "C25") (pin "1") (pinfunction "1_1") (pintype "passive"))
      (node (ref "C29") (pin "1") (pinfunction "1_1") (pintype "passive"))
      (node (ref "C30") (pin "+") (pinfunction "+_+") (pintype "passive"))
      (node (ref "KEY") (pin "5") (pinfunction "5_5") (pintype "passive"))
      (node (ref "L2") (pin "2") (pinfunction "2_2") (pintype "passive"))
      (node (ref "LP-INTERN") (pin "1") (pinfunction "1_1") (pintype "passive"))
      (node (ref "MOUSE") (pin "5") (pinfunction "5_5") (pintype "passive"))
      (node (ref "PLEXBUS") (pin "5") (pinfunction "5_5") (pintype "passive"))
      (node (ref "SD-CARD") (pin "3") (pinfunction "3_3") (pintype "passive"))
      (node (ref "TASTATUR") (pin "1") (pinfunction "1_1") (pintype "passive"))
    )
    (net (code "187") (name "VDD") (class "Default")
      (node (ref "ADM") (pin "8") (pinfunction "VCC_8") (pintype "power_in"))
      (node (ref "ADM-LED") (pin "2") (pinfunction "2_2") (pintype "passive"))
      (node (ref "BEL") (pin "8") (pinfunction "VCC_8") (pintype "power_in"))
      (node (ref "C1") (pin "1") (pinfunction "1_1") (pintype "passive"))
      (node (ref "C10") (pin "1") (pinfunction "1_1") (pintype "passive"))
      (node (ref "C11") (pin "1") (pinfunction "1_1") (pintype "passive"))
      (node (ref "C12") (pin "1") (pinfunction "1_1") (pintype "passive"))
      (node (ref "C17") (pin "1") (pinfunction "1_1") (pintype "passive"))
      (node (ref "C18") (pin "1") (pinfunction "1_1") (pintype "passive"))
      (node (ref "C19") (pin "1") (pinfunction "1_1") (pintype "passive"))
      (node (ref "C2") (pin "1") (pinfunction "1_1") (pintype "passive"))
      (node (ref "C20") (pin "1") (pinfunction "1_1") (pintype "passive"))
      (node (ref "C21") (pin "1") (pinfunction "1_1") (pintype "passive"))
      (node (ref "C23") (pin "1") (pinfunction "1_1") (pintype "passive"))
      (node (ref "C26") (pin "1") (pinfunction "1_1") (pintype "passive"))
      (node (ref "C27") (pin "1") (pinfunction "1_1") (pintype "passive"))
      (node (ref "C28") (pin "+") (pinfunction "+_+") (pintype "passive"))
      (node (ref "C3") (pin "1") (pinfunction "1_1") (pintype "passive"))
      (node (ref "C4") (pin "1") (pinfunction "1_1") (pintype "passive"))
      (node (ref "C5") (pin "1") (pinfunction "1_1") (pintype "passive"))
      (node (ref "C6") (pin "+") (pinfunction "+_+") (pintype "passive"))
      (node (ref "C7") (pin "1") (pinfunction "1_1") (pintype "passive"))
      (node (ref "C8") (pin "1") (pinfunction "1_1") (pintype "passive"))
      (node (ref "C9") (pin "1") (pinfunction "1_1") (pintype "passive"))
      (node (ref "ERW.INTERN") (pin "5") (pinfunction "5_5") (pintype "passive"))
      (node (ref "IC10") (pin "32") (pinfunction "VCC_32") (pintype "power_in"))
      (node (ref "IC13") (pin "1") (pinfunction "A0_1") (pintype "input"))
      (node (ref "IC13") (pin "16") (pinfunction "VDD_16") (pintype "power_in"))
      (node (ref "IC2") (pin "16") (pinfunction "VDD_16") (pintype "power_in"))
      (node (ref "IC3") (pin "6") (pinfunction "G1_6") (pintype "input"))
      (node (ref "IC8") (pin "32") (pinfunction "VCC_32") (pintype "power_in"))
      (node (ref "IC9") (pin "32") (pinfunction "VCC_32") (pintype "power_in"))
      (node (ref "JP2") (pin "1") (pinfunction "1_1") (pintype "passive"))
      (node (ref "JP3") (pin "1") (pinfunction "1_1") (pintype "passive"))
      (node (ref "L1") (pin "2") (pinfunction "2_2") (pintype "passive"))
      (node (ref "MICROMITE") (pin "6") (pinfunction "6_6") (pintype "passive"))
      (node (ref "PLEXBUS") (pin "4") (pinfunction "4_4") (pintype "passive"))
      (node (ref "R12") (pin "2") (pinfunction "2_2") (pintype "passive"))
      (node (ref "R13") (pin "2") (pinfunction "2_2") (pintype "passive"))
      (node (ref "R14") (pin "2") (pinfunction "2_2") (pintype "passive"))
      (node (ref "R15") (pin "2") (pinfunction "2_2") (pintype "passive"))
      (node (ref "R20") (pin "1") (pinfunction "1_1") (pintype "passive"))
      (node (ref "R21") (pin "1") (pinfunction "1_1") (pintype "passive"))
      (node (ref "R27") (pin "1") (pinfunction "1_1") (pintype "passive"))
      (node (ref "R28") (pin "1") (pinfunction "1_1") (pintype "passive"))
      (node (ref "R30") (pin "2") (pinfunction "2_2") (pintype "passive"))
      (node (ref "R34") (pin "1") (pinfunction "1_1") (pintype "passive"))
      (node (ref "R35") (pin "1") (pinfunction "1_1") (pintype "passive"))
      (node (ref "R36") (pin "1") (pinfunction "1_1") (pintype "passive"))
      (node (ref "R37") (pin "1") (pinfunction "1_1") (pintype "passive"))
      (node (ref "REG") (pin "8") (pinfunction "VCC_8") (pintype "power_in"))
      (node (ref "RN2") (pin "1") (pinfunction "1_1") (pintype "passive"))
      (node (ref "RN3") (pin "1") (pinfunction "1_1") (pintype "passive"))
      (node (ref "RN4") (pin "1") (pinfunction "1_1") (pintype "passive"))
      (node (ref "RTC") (pin "4") (pinfunction "4_4") (pintype "passive"))
      (node (ref "SD-CARD") (pin "2") (pinfunction "2_2") (pintype "passive"))
      (node (ref "U$1") (pin "41") (pinfunction "41_41") (pintype "passive"))
    )
    (net (code "188") (name "unconnected-(IC2-~{INT}-Pad13)") (class "Default")
      (node (ref "IC2") (pin "13") (pinfunction "~{INT}_13") (pintype "output"))
    )
    (net (code "189") (name "unconnected-(IC3A-Y5-Pad10)") (class "Default")
      (node (ref "IC3") (pin "10") (pinfunction "Y5_10") (pintype "output"))
    )
    (net (code "190") (name "unconnected-(IC3A-Y6-Pad9)") (class "Default")
      (node (ref "IC3") (pin "9") (pinfunction "Y6_9") (pintype "output"))
    )
    (net (code "191") (name "unconnected-(IC3A-Y7-Pad7)") (class "Default")
      (node (ref "IC3") (pin "7") (pinfunction "Y7_7") (pintype "output"))
    )
    (net (code "192") (name "unconnected-(IC7A-4Q-Pad9)") (class "Default")
      (node (ref "IC7") (pin "9") (pinfunction "4Q_9") (pintype "tri_state"))
    )
    (net (code "193") (name "unconnected-(IC7A-5Q-Pad12)") (class "Default")
      (node (ref "IC7") (pin "12") (pinfunction "5Q_12") (pintype "tri_state"))
    )
    (net (code "194") (name "unconnected-(IC7A-6Q-Pad15)") (class "Default")
      (node (ref "IC7") (pin "15") (pinfunction "6Q_15") (pintype "tri_state"))
    )
    (net (code "195") (name "unconnected-(IC7A-7Q-Pad16)") (class "Default")
      (node (ref "IC7") (pin "16") (pinfunction "7Q_16") (pintype "tri_state"))
    )
    (net (code "196") (name "unconnected-(IC7A-8Q-Pad19)") (class "Default")
      (node (ref "IC7") (pin "19") (pinfunction "8Q_19") (pintype "tri_state"))
    )
    (net (code "197") (name "unconnected-(IC13-~{INT}-Pad13)") (class "Default")
      (node (ref "IC13") (pin "13") (pinfunction "~{INT}_13") (pintype "output"))
    )
    (net (code "198") (name "unconnected-(KEY-Pad2)") (class "Default")
      (node (ref "KEY") (pin "2") (pinfunction "2_2") (pintype "passive"))
    )
    (net (code "199") (name "unconnected-(KEY-Pad8)") (class "Default")
      (node (ref "KEY") (pin "8") (pinfunction "8_8") (pintype "passive"))
    )
    (net (code "200") (name "unconnected-(MICROMITE-Pad5)") (class "Default")
      (node (ref "MICROMITE") (pin "5") (pinfunction "5_5") (pintype "passive"))
    )
    (net (code "201") (name "unconnected-(MOUSE-Pad2)") (class "Default")
      (node (ref "MOUSE") (pin "2") (pinfunction "2_2") (pintype "passive"))
    )
    (net (code "202") (name "unconnected-(MOUSE-Pad8)") (class "Default")
      (node (ref "MOUSE") (pin "8") (pinfunction "8_8") (pintype "passive"))
    )
    (net (code "203") (name "unconnected-(RN3-Pad8)") (class "Default")
      (node (ref "RN3") (pin "8") (pinfunction "8_8") (pintype "passive"))
    )
    (net (code "204") (name "unconnected-(U$1-Pad20)") (class "Default")
      (node (ref "U$1") (pin "20") (pinfunction "20_20") (pintype "passive"))
    )
    (net (code "205") (name "unconnected-(V51D-Y-Pad6)") (class "Default")
      (node (ref "V51") (pin "6") (pinfunction "Y_6") (pintype "output"))
    )
    (net (code "206") (name "unconnected-(V51E-Y-Pad8)") (class "Default")
      (node (ref "V51") (pin "8") (pinfunction "Y_8") (pintype "output"))
    )
    (net (code "207") (name "unconnected-(V51F-Y-Pad11)") (class "Default")
      (node (ref "V51") (pin "11") (pinfunction "Y_11") (pintype "output"))
    )
    (net (code "208") (name "unconnected-(X5-Pad4)") (class "Default")
      (node (ref "X5") (pin "4") (pinfunction "4_4") (pintype "passive"))
    )
    (net (code "209") (name "unconnected-(X5-Pad5)") (class "Default")
      (node (ref "X5") (pin "5") (pinfunction "5_5") (pintype "passive"))
    )
    (net (code "210") (name "unconnected-(X5-Pad11)") (class "Default")
      (node (ref "X5") (pin "11") (pinfunction "11_11") (pintype "passive"))
    )
    (net (code "211") (name "unconnected-(X5-Pad12)") (class "Default")
      (node (ref "X5") (pin "12") (pinfunction "12_12") (pintype "passive"))
    )
    (net (code "212") (name "unconnected-(X5-Pad15)") (class "Default")
      (node (ref "X5") (pin "15") (pinfunction "15_15") (pintype "passive"))
    )
  )
)
